# PA_Combined_RX_TX.net
KiCad netlist of a schematic drawn in Altium Designer
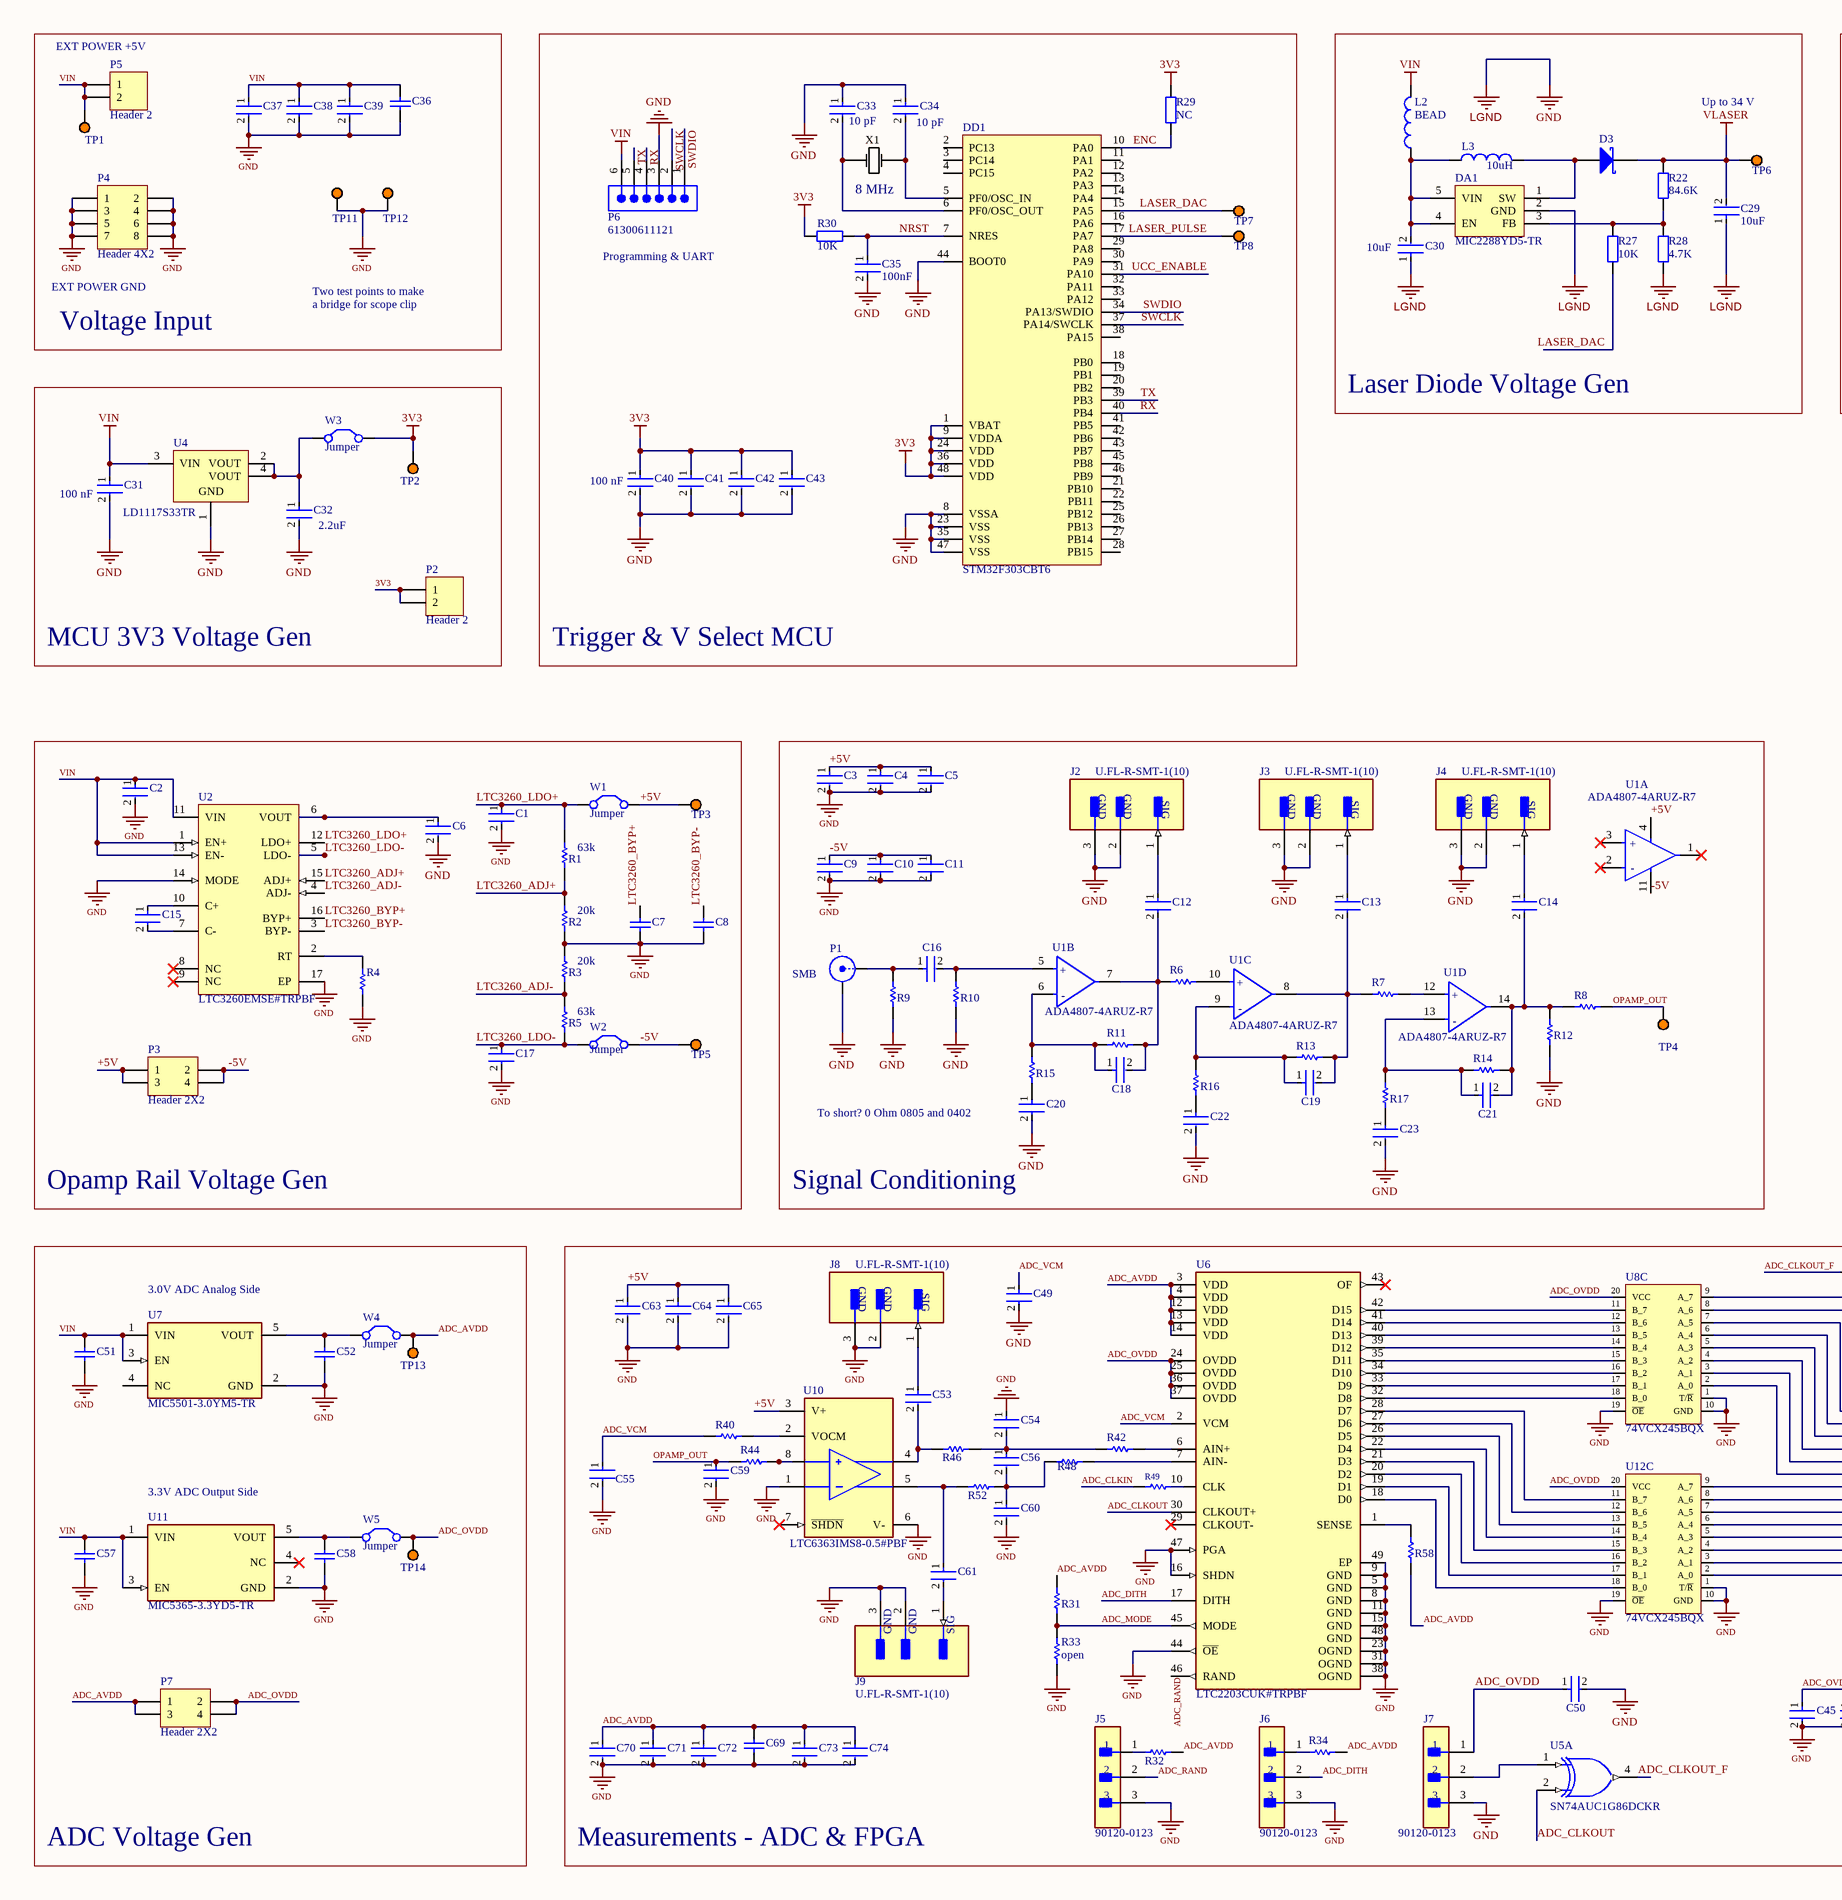
[diagram p0: PA_Combined_RX_TX.SchDoc, left]
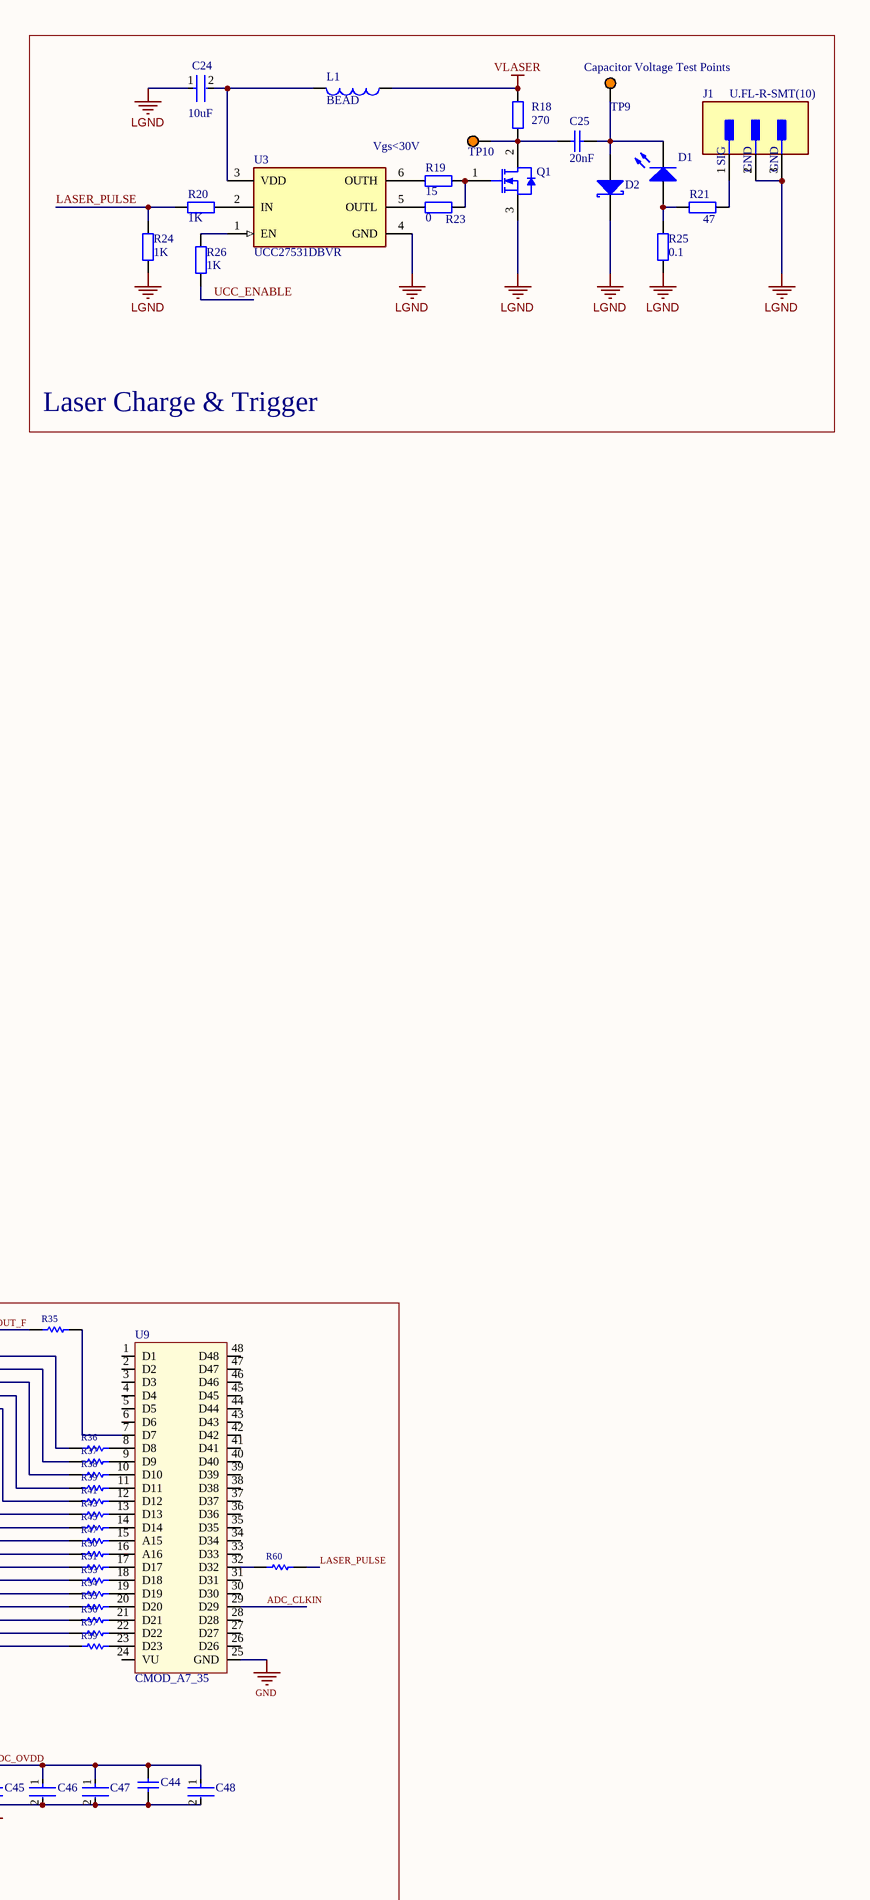
[diagram p1: PA_Combined_RX_TX.SchDoc, right]

(export (version "E")
  (design (tool "Eeschema 10.0.6"))
  (components
    (comp (ref "C1")
      (value "CL21B106KOQNNNG")
      (footprint "FP-CL21B106KOQNNNG-MFG")
      (description "CAP CER 10UF 16V X7R 0805")
      (fields
        (field (name "TOLERANCE") "10%")
        (field (name "OCTOPART") "https://octopart.com/cl21b106koqnnng-samsung-19995691")
      )
      (libsource (lib "Altium Content Vault") (part "b4654b650e69147ec39a6b967a45e02"))
    )
    (comp (ref "C2")
      (value "CL21B106KOQNNNG")
      (footprint "FP-CL21B106KOQNNNG-MFG")
      (description "CAP CER 10UF 16V X7R 0805")
      (fields
        (field (name "TOLERANCE") "10%")
        (field (name "OCTOPART") "https://octopart.com/cl21b106koqnnng-samsung-19995691")
      )
      (libsource (lib "Altium Content Vault") (part "b4654b650e69147ec39a6b967a45e02"))
    )
    (comp (ref "C3")
      (value "CL21B106KOQNNNG")
      (footprint "FP-CL21B106KOQNNNG-MFG")
      (description "CAP CER 10UF 16V X7R 0805")
      (fields
        (field (name "TOLERANCE") "10%")
        (field (name "OCTOPART") "https://octopart.com/cl21b106koqnnng-samsung-19995691")
      )
      (libsource (lib "Altium Content Vault") (part "b4654b650e69147ec39a6b967a45e02"))
    )
    (comp (ref "C4")
      (value "GRM21BR71C475KE51K")
      (footprint "FP-GRM21B-0_15-MFG")
      (description "Chip Multilayer Ceramic Capacitors for General Purpose, 0805, 4.7uF, X7R, 15%, 10%, 16V")
      (fields (field (name "TOLERANCE") "10%"))
      (libsource (lib "Altium Content Vault") (part "b4654b650e69147ec39a6b967a45e02"))
    )
    (comp (ref "C5")
      (value "C0805C104K5RACTU")
      (footprint "FP-C0805C-DN-MFG")
      (description "CAP CER 0.1UF 50V X7R 0805")
      (fields
        (field (name "MANUFACTURER") "KEMET")
        (field (name "OCTOPART") "https://octopart.com/c0805c104k5ractu-kemet-143926")
      )
      (libsource (lib "Altium Content Vault") (part "b4654b650e69147ec39a6b967a45e02"))
    )
    (comp (ref "C6")
      (value "CL21B106KOQNNNG")
      (footprint "FP-CL21B106KOQNNNG-MFG")
      (description "CAP CER 10UF 16V X7R 0805")
      (fields
        (field (name "TOLERANCE") "10%")
        (field (name "OCTOPART") "https://octopart.com/cl21b106koqnnng-samsung-19995691")
      )
      (libsource (lib "Altium Content Vault") (part "b4654b650e69147ec39a6b967a45e02"))
    )
    (comp (ref "C7")
      (value "C0805F103K5RACTU")
      (footprint "CAPC2013X100X50NL20T25")
      (fields (field (name "MANUFACTURER") "Kemet"))
      (libsource (lib "Altium Content Vault") (part "CAP"))
    )
    (comp (ref "C8")
      (value "C0805F103K5RACTU")
      (footprint "CAPC2013X100X50NL20T25")
      (fields (field (name "MANUFACTURER") "Kemet"))
      (libsource (lib "Altium Content Vault") (part "CAP"))
    )
    (comp (ref "C9")
      (value "CL21B106KOQNNNG")
      (footprint "FP-CL21B106KOQNNNG-MFG")
      (description "CAP CER 10UF 16V X7R 0805")
      (fields
        (field (name "TOLERANCE") "10%")
        (field (name "OCTOPART") "https://octopart.com/cl21b106koqnnng-samsung-19995691")
      )
      (libsource (lib "Altium Content Vault") (part "b4654b650e69147ec39a6b967a45e02"))
    )
    (comp (ref "C10")
      (value "GRM21BR71C475KE51K")
      (footprint "FP-GRM21B-0_15-MFG")
      (description "Chip Multilayer Ceramic Capacitors for General Purpose, 0805, 4.7uF, X7R, 15%, 10%, 16V")
      (fields (field (name "TOLERANCE") "10%"))
      (libsource (lib "Altium Content Vault") (part "b4654b650e69147ec39a6b967a45e02"))
    )
    (comp (ref "C11")
      (value "C0805C104K5RACTU")
      (footprint "FP-C0805C-DN-MFG")
      (description "CAP CER 0.1UF 50V X7R 0805")
      (fields
        (field (name "MANUFACTURER") "KEMET")
        (field (name "OCTOPART") "https://octopart.com/c0805c104k5ractu-kemet-143926")
      )
      (libsource (lib "Altium Content Vault") (part "b4654b650e69147ec39a6b967a45e02"))
    )
    (comp (ref "C12")
      (value "C0805C102K5RACTU")
      (footprint "FP-C0805C-DN-MFG")
      (description "CAP CER 1000PF 50V X7R 0805")
      (fields
        (field (name "OCTOPART") "https://octopart.com/c0805c102k5ractu-kemet-93010")
        (field (name "TOLERANCE") "0.1")
      )
      (libsource (lib "Altium Content Vault") (part "b4654b650e69147ec39a6b967a45e02"))
    )
    (comp (ref "C13")
      (value "C0805C102K5RACTU")
      (footprint "FP-C0805C-DN-MFG")
      (description "CAP CER 1000PF 50V X7R 0805")
      (fields
        (field (name "OCTOPART") "https://octopart.com/c0805c102k5ractu-kemet-93010")
        (field (name "TOLERANCE") "0.1")
      )
      (libsource (lib "Altium Content Vault") (part "b4654b650e69147ec39a6b967a45e02"))
    )
    (comp (ref "C14")
      (value "C0805C102K5RACTU")
      (footprint "FP-C0805C-DN-MFG")
      (description "CAP CER 1000PF 50V X7R 0805")
      (fields
        (field (name "OCTOPART") "https://octopart.com/c0805c102k5ractu-kemet-93010")
        (field (name "TOLERANCE") "0.1")
      )
      (libsource (lib "Altium Content Vault") (part "b4654b650e69147ec39a6b967a45e02"))
    )
    (comp (ref "C15")
      (value "CL21B105KAFNNNG")
      (footprint "FP-CL21-IPC_C")
      (description "CL21 Series 0805 1uF 25V ±10% Tolerance X7R Multilayer Ceramic Chip Capacitor")
      (fields (field (name "TOLERANCE") "10%") (field (name "VOLTAGE") "25V"))
      (libsource (lib "Altium Content Vault") (part "b4654b650e69147ec39a6b967a45e02"))
    )
    (comp (ref "C16")
      (value "CL21B222JBANNNC")
      (footprint "FP-CL21-IPC_B")
      (description "CL21 Series 0805 2.2nF 50V ±5% Tolerance X7R Multilayer Ceramic Chip Capacitor")
      (fields (field (name "TOLERANCE") "5%") (field (name "VOLTAGE") "50V"))
      (libsource (lib "Altium Content Vault") (part "b4654b650e69147ec39a6b967a45e02"))
    )
    (comp (ref "C17")
      (value "CL21B106KOQNNNG")
      (footprint "FP-CL21B106KOQNNNG-MFG")
      (description "CAP CER 10UF 16V X7R 0805")
      (fields
        (field (name "TOLERANCE") "10%")
        (field (name "OCTOPART") "https://octopart.com/cl21b106koqnnng-samsung-19995691")
      )
      (libsource (lib "Altium Content Vault") (part "b4654b650e69147ec39a6b967a45e02"))
    )
    (comp (ref "C18")
      (value "C0805C150K5RACTU")
      (footprint "FP-C0805C-DN-MFG")
      (description "CAP CER SMD 0805 15PF 50V 10% X7")
      (fields
        (field (name "OCTOPART") "https://octopart.com/c0805c150k5ractu-kemet-88373275")
        (field (name "MANUFACTURER") "KEMET")
      )
      (libsource (lib "Altium Content Vault") (part "b4654b650e69147ec39a6b967a45e02"))
    )
    (comp (ref "C19")
      (value "C0805C150K5RACTU")
      (footprint "FP-C0805C-DN-MFG")
      (description "CAP CER SMD 0805 15PF 50V 10% X7")
      (fields
        (field (name "OCTOPART") "https://octopart.com/c0805c150k5ractu-kemet-88373275")
        (field (name "MANUFACTURER") "KEMET")
      )
      (libsource (lib "Altium Content Vault") (part "b4654b650e69147ec39a6b967a45e02"))
    )
    (comp (ref "C20")
      (value "CL21B106KOQNNNG")
      (footprint "FP-CL21B106KOQNNNG-MFG")
      (description "CAP CER 10UF 16V X7R 0805")
      (fields
        (field (name "TOLERANCE") "10%")
        (field (name "OCTOPART") "https://octopart.com/cl21b106koqnnng-samsung-19995691")
      )
      (libsource (lib "Altium Content Vault") (part "b4654b650e69147ec39a6b967a45e02"))
    )
    (comp (ref "C21")
      (value "C0805C150K5RACTU")
      (footprint "FP-C0805C-DN-MFG")
      (description "CAP CER SMD 0805 15PF 50V 10% X7")
      (fields
        (field (name "OCTOPART") "https://octopart.com/c0805c150k5ractu-kemet-88373275")
        (field (name "MANUFACTURER") "KEMET")
      )
      (libsource (lib "Altium Content Vault") (part "b4654b650e69147ec39a6b967a45e02"))
    )
    (comp (ref "C22")
      (value "CL21B106KOQNNNG")
      (footprint "FP-CL21B106KOQNNNG-MFG")
      (description "CAP CER 10UF 16V X7R 0805")
      (fields
        (field (name "TOLERANCE") "10%")
        (field (name "OCTOPART") "https://octopart.com/cl21b106koqnnng-samsung-19995691")
      )
      (libsource (lib "Altium Content Vault") (part "b4654b650e69147ec39a6b967a45e02"))
    )
    (comp (ref "C23")
      (value "CL21B106KOQNNNG")
      (footprint "FP-CL21B106KOQNNNG-MFG")
      (description "CAP CER 10UF 16V X7R 0805")
      (fields
        (field (name "TOLERANCE") "10%")
        (field (name "OCTOPART") "https://octopart.com/cl21b106koqnnng-samsung-19995691")
      )
      (libsource (lib "Altium Content Vault") (part "b4654b650e69147ec39a6b967a45e02"))
    )
    (comp (ref "C24")
      (value "10uF")
      (footprint "FP-CL31B106KBHNNNE-MFG")
      (description "CAP CER 10UF 50V X7R 1206")
      (fields (field (name "MANUFACTURER") "Samsung") (field (name "TOLERANCE") "10%"))
      (libsource (lib "Altium Content Vault") (part "b4654b650e69147ec39a6b967a45e02"))
    )
    (comp (ref "C25")
      (value "20nF")
      (footprint "RESC2013X60X35ML10T20")
      (description "Chip capacitor")
      (fields (field (name "VOLTAGE") "50V"))
      (libsource (lib "MyLibSch") (part "CC0805"))
    )
    (comp (ref "C29")
      (value "10uF")
      (footprint "FP-CL31B106KBHNNNE-MFG")
      (description "CAP CER 10UF 50V X7R 1206")
      (fields (field (name "MANUFACTURER") "Samsung") (field (name "TOLERANCE") "10%"))
      (libsource (lib "Altium Content Vault") (part "b4654b650e69147ec39a6b967a45e02"))
    )
    (comp (ref "C30")
      (value "10uF")
      (footprint "FP-CL31B106KBHNNNE-MFG")
      (description "CAP CER 10UF 50V X7R 1206")
      (fields (field (name "MANUFACTURER") "Samsung") (field (name "TOLERANCE") "10%"))
      (libsource (lib "Altium Content Vault") (part "b4654b650e69147ec39a6b967a45e02"))
    )
    (comp (ref "C31")
      (value "100 nF")
      (footprint "FP-CC0603-DA-MFG")
      (description "CAP CER 0.1UF 16V X7R 0603")
      (fields
        (field (name "OCTOPART") "https://octopart.com/cc0603krx7r7bb104-yageo-192941")
        (field (name "TOLERANCE") "0.1")
      )
      (libsource (lib "Altium Content Vault") (part "11868f565c42a9108669ba33697ecf6"))
    )
    (comp (ref "C32")
      (value "~")
      (footprint "FP-CL10-IPC_A")
      (description "Cap Ceramic 2.2uF 10V X7R ±10% Pad SMD 0603 +125°C T/R")
      (fields (field (name "CAPACITANCE") "2.2uF") (field (name "TOLERANCE") "10%"))
      (libsource (lib "Altium Content Vault") (part "b4654b650e69147ec39a6b967a45e02"))
    )
    (comp (ref "C33")
      (value "10 pF")
      (footprint "FP-C0805C-DN-MFG")
      (description "C0805 10 pF X7R 30ppm/°C 5.00% 50 V")
      (fields
        (field (name "OCTOPART") "https://octopart.com/c0805c100j5ractu-kemet-81794931")
        (field (name "MANUFACTURER PART NUMBER") "C0805C100J5RACTU")
      )
      (libsource (lib "Altium Content Vault") (part "b4654b650e69147ec39a6b967a45e02"))
    )
    (comp (ref "C34")
      (value "10 pF")
      (footprint "FP-C0805C-DN-MFG")
      (description "C0805 10 pF X7R 30ppm/°C 5.00% 50 V")
      (fields
        (field (name "OCTOPART") "https://octopart.com/c0805c100j5ractu-kemet-81794931")
        (field (name "MANUFACTURER PART NUMBER") "C0805C100J5RACTU")
      )
      (libsource (lib "Altium Content Vault") (part "b4654b650e69147ec39a6b967a45e02"))
    )
    (comp (ref "C35")
      (value "100nF")
      (footprint "FP-CC0805-0_85-MFG")
      (description "CAP CER 0.1UF 50V X7R 0805")
      (fields (field (name "TOLERANCE") "0.1") (field (name "MANUFACTURER PART NUMBER") "CC0805KRX7R9BB104"))
      (libsource (lib "Altium Content Vault") (part "11868f565c42a9108669ba33697ecf6"))
    )
    (comp (ref "C36")
      (value "C0805C105K3RACTU")
      (footprint "CAPC2013X140X50LL20T25")
      (fields (field (name "MANUFACTURER") "Kemet"))
      (libsource (lib "Altium Content Vault") (part "CAP"))
    )
    (comp (ref "C37")
      (value "CL21B106KOQNNNG")
      (footprint "FP-CL21B106KOQNNNG-MFG")
      (description "CAP CER 10UF 16V X7R 0805")
      (fields
        (field (name "TOLERANCE") "10%")
        (field (name "OCTOPART") "https://octopart.com/cl21b106koqnnng-samsung-19995691")
      )
      (libsource (lib "Altium Content Vault") (part "b4654b650e69147ec39a6b967a45e02"))
    )
    (comp (ref "C38")
      (value "GRM21BR71C475KE51K")
      (footprint "FP-GRM21B-0_15-MFG")
      (description "Chip Multilayer Ceramic Capacitors for General Purpose, 0805, 4.7uF, X7R, 15%, 10%, 16V")
      (fields (field (name "TOLERANCE") "10%"))
      (libsource (lib "Altium Content Vault") (part "b4654b650e69147ec39a6b967a45e02"))
    )
    (comp (ref "C39")
      (value "C0805C104K5RACTU")
      (footprint "FP-C0805C-DN-MFG")
      (description "CAP CER 0.1UF 50V X7R 0805")
      (fields
        (field (name "MANUFACTURER") "KEMET")
        (field (name "OCTOPART") "https://octopart.com/c0805c104k5ractu-kemet-143926")
      )
      (libsource (lib "Altium Content Vault") (part "b4654b650e69147ec39a6b967a45e02"))
    )
    (comp (ref "C40")
      (value "CC0805KRX7R9BB104")
      (footprint "FP-CC0805-0_85-MFG")
      (description "CAP CER 0.1UF 50V X7R 0805")
      (fields
        (field (name "TOLERANCE") "0.1")
        (field (name "CAPACITANCE") "100 nF")
        (field (name "MANUFACTURER") "Yageo")
      )
      (libsource (lib "Altium Content Vault") (part "11868f565c42a9108669ba33697ecf6"))
    )
    (comp (ref "C41")
      (value "CC0805KRX7R9BB104")
      (footprint "FP-CC0805-0_85-MFG")
      (description "CAP CER 0.1UF 50V X7R 0805")
      (fields (field (name "TOLERANCE") "0.1") (field (name "MANUFACTURER") "Yageo"))
      (libsource (lib "Altium Content Vault") (part "11868f565c42a9108669ba33697ecf6"))
    )
    (comp (ref "C42")
      (value "CC0805KRX7R9BB104")
      (footprint "FP-CC0805-0_85-MFG")
      (description "CAP CER 0.1UF 50V X7R 0805")
      (fields (field (name "TOLERANCE") "0.1") (field (name "MANUFACTURER") "Yageo"))
      (libsource (lib "Altium Content Vault") (part "11868f565c42a9108669ba33697ecf6"))
    )
    (comp (ref "C43")
      (value "CC0805KRX7R9BB104")
      (footprint "FP-CC0805-0_85-MFG")
      (description "CAP CER 0.1UF 50V X7R 0805")
      (fields (field (name "TOLERANCE") "0.1") (field (name "MANUFACTURER") "Yageo"))
      (libsource (lib "Altium Content Vault") (part "11868f565c42a9108669ba33697ecf6"))
    )
    (comp (ref "C44")
      (value "C0805C105K3RACTU")
      (footprint "CAPC2013X140X50LL20T25")
      (fields (field (name "MANUFACTURER") "Kemet"))
      (libsource (lib "Altium Content Vault") (part "CAP"))
    )
    (comp (ref "C45")
      (value "CL21B106KOQNNNG")
      (footprint "FP-CL21B106KOQNNNG-MFG")
      (description "CAP CER 10UF 16V X7R 0805")
      (fields
        (field (name "TOLERANCE") "10%")
        (field (name "OCTOPART") "https://octopart.com/cl21b106koqnnng-samsung-19995691")
      )
      (libsource (lib "Altium Content Vault") (part "b4654b650e69147ec39a6b967a45e02"))
    )
    (comp (ref "C46")
      (value "GRM21BR71C475KE51K")
      (footprint "FP-GRM21B-0_15-MFG")
      (description "Chip Multilayer Ceramic Capacitors for General Purpose, 0805, 4.7uF, X7R, 15%, 10%, 16V")
      (fields (field (name "TOLERANCE") "10%"))
      (libsource (lib "Altium Content Vault") (part "b4654b650e69147ec39a6b967a45e02"))
    )
    (comp (ref "C47")
      (value "C0805C104K5RACTU")
      (footprint "FP-C0805C-DN-MFG")
      (description "CAP CER 0.1UF 50V X7R 0805")
      (fields
        (field (name "MANUFACTURER") "KEMET")
        (field (name "OCTOPART") "https://octopart.com/c0805c104k5ractu-kemet-143926")
      )
      (libsource (lib "Altium Content Vault") (part "b4654b650e69147ec39a6b967a45e02"))
    )
    (comp (ref "C48")
      (value "C0805C104K5RACTU")
      (footprint "FP-C0805C-DN-MFG")
      (description "CAP CER 0.1UF 50V X7R 0805")
      (fields
        (field (name "MANUFACTURER") "KEMET")
        (field (name "OCTOPART") "https://octopart.com/c0805c104k5ractu-kemet-143926")
      )
      (libsource (lib "Altium Content Vault") (part "b4654b650e69147ec39a6b967a45e02"))
    )
    (comp (ref "C49")
      (value "C2012X7R1C225K125AB")
      (footprint "FP-C2012-125-0_2-MFG")
      (description "Multilayer Ceramic Capacitors 2.2μF ±10% 16V X7R SMD 0805")
      (fields (field (name "TOLERANCE") "10%") (field (name "VOLTAGE") "16V"))
      (libsource (lib "Altium Content Vault") (part "b4654b650e69147ec39a6b967a45e02"))
    )
    (comp (ref "C50")
      (value "C0805C104K5RACTU")
      (footprint "FP-C0805C-DN-MFG")
      (description "CAP CER 0.1UF 50V X7R 0805")
      (fields
        (field (name "MANUFACTURER") "KEMET")
        (field (name "OCTOPART") "https://octopart.com/c0805c104k5ractu-kemet-143926")
      )
      (libsource (lib "Altium Content Vault") (part "b4654b650e69147ec39a6b967a45e02"))
    )
    (comp (ref "C51")
      (value "C0805C105K3RACTU")
      (footprint "CAPC2013X140X50LL20T25")
      (fields (field (name "MANUFACTURER") "Kemet"))
      (libsource (lib "Altium Content Vault") (part "CAP"))
    )
    (comp (ref "C52")
      (value "C0805C105K3RACTU")
      (footprint "CAPC2013X140X50LL20T25")
      (fields (field (name "MANUFACTURER") "Kemet"))
      (libsource (lib "Altium Content Vault") (part "CAP"))
    )
    (comp (ref "C53")
      (value "C0805C102K5RACTU")
      (footprint "FP-C0805C-DN-MFG")
      (description "CAP CER 1000PF 50V X7R 0805")
      (fields
        (field (name "OCTOPART") "https://octopart.com/c0805c102k5ractu-kemet-93010")
        (field (name "TOLERANCE") "0.1")
      )
      (libsource (lib "Altium Content Vault") (part "b4654b650e69147ec39a6b967a45e02"))
    )
    (comp (ref "C54")
      (value "C0805C100J5RACTU")
      (footprint "FP-C0805C-DN-MFG")
      (description "C0805 10 pF X7R 30ppm/°C 5.00% 50 V")
      (fields
        (field (name "OCTOPART") "https://octopart.com/c0805c100j5ractu-kemet-81794931")
        (field (name "MANUFACTURER") "KEMET")
      )
      (libsource (lib "Altium Content Vault") (part "b4654b650e69147ec39a6b967a45e02"))
    )
    (comp (ref "C55")
      (value "C0805C104K5RACTU")
      (footprint "FP-C0805C-DN-MFG")
      (description "CAP CER 0.1UF 50V X7R 0805")
      (fields
        (field (name "MANUFACTURER") "KEMET")
        (field (name "OCTOPART") "https://octopart.com/c0805c104k5ractu-kemet-143926")
      )
      (libsource (lib "Altium Content Vault") (part "b4654b650e69147ec39a6b967a45e02"))
    )
    (comp (ref "C56")
      (value "C0805C100J5RACTU")
      (footprint "FP-C0805C-DN-MFG")
      (description "C0805 10 pF X7R 30ppm/°C 5.00% 50 V")
      (fields
        (field (name "OCTOPART") "https://octopart.com/c0805c100j5ractu-kemet-81794931")
        (field (name "MANUFACTURER") "KEMET")
      )
      (libsource (lib "Altium Content Vault") (part "b4654b650e69147ec39a6b967a45e02"))
    )
    (comp (ref "C57")
      (value "C0805C105K3RACTU")
      (footprint "CAPC2013X140X50LL20T25")
      (fields (field (name "MANUFACTURER") "Kemet"))
      (libsource (lib "Altium Content Vault") (part "CAP"))
    )
    (comp (ref "C58")
      (value "C0805C105K3RACTU")
      (footprint "CAPC2013X140X50LL20T25")
      (fields (field (name "MANUFACTURER") "Kemet"))
      (libsource (lib "Altium Content Vault") (part "CAP"))
    )
    (comp (ref "C59")
      (value "C0805C100J5RACTU")
      (footprint "FP-C0805C-DN-MFG")
      (description "C0805 10 pF X7R 30ppm/°C 5.00% 50 V")
      (fields
        (field (name "OCTOPART") "https://octopart.com/c0805c100j5ractu-kemet-81794931")
        (field (name "MANUFACTURER") "KEMET")
      )
      (libsource (lib "Altium Content Vault") (part "b4654b650e69147ec39a6b967a45e02"))
    )
    (comp (ref "C60")
      (value "C0805C100J5RACTU")
      (footprint "FP-C0805C-DN-MFG")
      (description "C0805 10 pF X7R 30ppm/°C 5.00% 50 V")
      (fields
        (field (name "OCTOPART") "https://octopart.com/c0805c100j5ractu-kemet-81794931")
        (field (name "MANUFACTURER") "KEMET")
      )
      (libsource (lib "Altium Content Vault") (part "b4654b650e69147ec39a6b967a45e02"))
    )
    (comp (ref "C61")
      (value "C0805C102K5RACTU")
      (footprint "FP-C0805C-DN-MFG")
      (description "CAP CER 1000PF 50V X7R 0805")
      (fields
        (field (name "OCTOPART") "https://octopart.com/c0805c102k5ractu-kemet-93010")
        (field (name "TOLERANCE") "0.1")
      )
      (libsource (lib "Altium Content Vault") (part "b4654b650e69147ec39a6b967a45e02"))
    )
    (comp (ref "C63")
      (value "CL21B106KOQNNNG")
      (footprint "FP-CL21B106KOQNNNG-MFG")
      (description "CAP CER 10UF 16V X7R 0805")
      (fields
        (field (name "TOLERANCE") "10%")
        (field (name "OCTOPART") "https://octopart.com/cl21b106koqnnng-samsung-19995691")
      )
      (libsource (lib "Altium Content Vault") (part "b4654b650e69147ec39a6b967a45e02"))
    )
    (comp (ref "C64")
      (value "GRM21BR71C475KE51K")
      (footprint "FP-GRM21B-0_15-MFG")
      (description "Chip Multilayer Ceramic Capacitors for General Purpose, 0805, 4.7uF, X7R, 15%, 10%, 16V")
      (fields (field (name "TOLERANCE") "10%"))
      (libsource (lib "Altium Content Vault") (part "b4654b650e69147ec39a6b967a45e02"))
    )
    (comp (ref "C65")
      (value "C0805C104K5RACTU")
      (footprint "FP-C0805C-DN-MFG")
      (description "CAP CER 0.1UF 50V X7R 0805")
      (fields
        (field (name "MANUFACTURER") "KEMET")
        (field (name "OCTOPART") "https://octopart.com/c0805c104k5ractu-kemet-143926")
      )
      (libsource (lib "Altium Content Vault") (part "b4654b650e69147ec39a6b967a45e02"))
    )
    (comp (ref "C69")
      (value "C0805C105K3RACTU")
      (footprint "CAPC2013X140X50LL20T25")
      (fields (field (name "MANUFACTURER") "Kemet"))
      (libsource (lib "Altium Content Vault") (part "CAP"))
    )
    (comp (ref "C70")
      (value "CL21B106KOQNNNG")
      (footprint "FP-CL21B106KOQNNNG-MFG")
      (description "CAP CER 10UF 16V X7R 0805")
      (fields
        (field (name "TOLERANCE") "10%")
        (field (name "OCTOPART") "https://octopart.com/cl21b106koqnnng-samsung-19995691")
      )
      (libsource (lib "Altium Content Vault") (part "b4654b650e69147ec39a6b967a45e02"))
    )
    (comp (ref "C71")
      (value "GRM21BR71C475KE51K")
      (footprint "FP-GRM21B-0_15-MFG")
      (description "Chip Multilayer Ceramic Capacitors for General Purpose, 0805, 4.7uF, X7R, 15%, 10%, 16V")
      (fields (field (name "TOLERANCE") "10%"))
      (libsource (lib "Altium Content Vault") (part "b4654b650e69147ec39a6b967a45e02"))
    )
    (comp (ref "C72")
      (value "C0805C104K5RACTU")
      (footprint "FP-C0805C-DN-MFG")
      (description "CAP CER 0.1UF 50V X7R 0805")
      (fields
        (field (name "MANUFACTURER") "KEMET")
        (field (name "OCTOPART") "https://octopart.com/c0805c104k5ractu-kemet-143926")
      )
      (libsource (lib "Altium Content Vault") (part "b4654b650e69147ec39a6b967a45e02"))
    )
    (comp (ref "C73")
      (value "C0805C104K5RACTU")
      (footprint "FP-C0805C-DN-MFG")
      (description "CAP CER 0.1UF 50V X7R 0805")
      (fields
        (field (name "MANUFACTURER") "KEMET")
        (field (name "OCTOPART") "https://octopart.com/c0805c104k5ractu-kemet-143926")
      )
      (libsource (lib "Altium Content Vault") (part "b4654b650e69147ec39a6b967a45e02"))
    )
    (comp (ref "C74")
      (value "C0805C104K5RACTU")
      (footprint "FP-C0805C-DN-MFG")
      (description "CAP CER 0.1UF 50V X7R 0805")
      (fields
        (field (name "MANUFACTURER") "KEMET")
        (field (name "OCTOPART") "https://octopart.com/c0805c104k5ractu-kemet-143926")
      )
      (libsource (lib "Altium Content Vault") (part "b4654b650e69147ec39a6b967a45e02"))
    )
    (comp (ref "D1")
      (value "Light-Emitting Diode")
      (footprint "FP-DPGEW1S09H-MFG")
      (libsource (lib "Simulation Generic Components") (part "LED"))
    )
    (comp (ref "D2")
      (value "Schottky Diode")
      (footprint "FP-PG-SC79-2-MFG")
      (libsource (lib "Simulation Generic Components") (part "Schottky Diode"))
    )
    (comp (ref "D3")
      (value "Schottky Diode")
      (footprint "FP-PG-SC79-2-MFG")
      (libsource (lib "Simulation Generic Components") (part "Schottky Diode"))
    )
    (comp (ref "DA1")
      (value "MIC2288YD5-TR")
      (footprint "TSOT-23-5:FP-TSOT-5LD-PL-1-IPC_A")
      (description "Step Up")
      (libsource (lib "lcd_lib") (part "MIC2288"))
    )
    (comp (ref "DD1")
      (value "STM32F303CBT6")
      (footprint "STM-LQFP48_L")
      (description "Microcontroller")
      (libsource (lib "lcd_lib") (part "STM32F3_LQFP48"))
    )
    (comp (ref "J1")
      (value "U.FL-R-SMT(10)")
      (footprint "FP-U_FL-R-SMT_10-MFG")
      (description "CONN U.FL RCPT STR 50 OHM SMD")
      (libsource (lib "Altium Content Vault") (part "eef6fde44c591823e8076210edfe12f"))
    )
    (comp (ref "J2")
      (value "U.FL-R-SMT-1(10)")
      (footprint "FP-U_FL-R-SMT-1_10-MFG")
      (description "CONN U.FL RCPT STR 50 OHM SMD")
      (libsource (lib "Altium Content Vault") (part "7158abf7d987fa84906f6fb0d115710"))
    )
    (comp (ref "J3")
      (value "U.FL-R-SMT-1(10)")
      (footprint "FP-U_FL-R-SMT-1_10-MFG")
      (description "CONN U.FL RCPT STR 50 OHM SMD")
      (libsource (lib "Altium Content Vault") (part "7158abf7d987fa84906f6fb0d115710"))
    )
    (comp (ref "J4")
      (value "U.FL-R-SMT-1(10)")
      (footprint "FP-U_FL-R-SMT-1_10-MFG")
      (description "CONN U.FL RCPT STR 50 OHM SMD")
      (libsource (lib "Altium Content Vault") (part "7158abf7d987fa84906f6fb0d115710"))
    )
    (comp (ref "J5")
      (value "90120-0123")
      (footprint "FP-90120-0123-MFG")
      (description "CONN HEADER VERT 3POS 2.54MM")
      (libsource (lib "Altium Content Vault") (part "0d3f023dd272f625e17a2be33dea85f"))
    )
    (comp (ref "J6")
      (value "90120-0123")
      (footprint "FP-90120-0123-MFG")
      (description "CONN HEADER VERT 3POS 2.54MM")
      (libsource (lib "Altium Content Vault") (part "0d3f023dd272f625e17a2be33dea85f"))
    )
    (comp (ref "J7")
      (value "90120-0123")
      (footprint "FP-90120-0123-MFG")
      (description "CONN HEADER VERT 3POS 2.54MM")
      (libsource (lib "Altium Content Vault") (part "0d3f023dd272f625e17a2be33dea85f"))
    )
    (comp (ref "J8")
      (value "U.FL-R-SMT-1(10)")
      (footprint "FP-U_FL-R-SMT-1_10-MFG")
      (description "CONN U.FL RCPT STR 50 OHM SMD")
      (libsource (lib "Altium Content Vault") (part "7158abf7d987fa84906f6fb0d115710"))
    )
    (comp (ref "J9")
      (value "U.FL-R-SMT-1(10)")
      (footprint "FP-U_FL-R-SMT-1_10-MFG")
      (description "CONN U.FL RCPT STR 50 OHM SMD")
      (libsource (lib "") (part "7158abf7d987fa84906f6fb0d115710_1"))
    )
    (comp (ref "L1")
      (value "BEAD")
      (footprint "FP-BLM18-0_15-t0_8-IPC_A")
      (description "Ferrit Bead")
      (libsource (lib "MyLibSch") (part "BEAD"))
    )
    (comp (ref "L2")
      (value "BEAD")
      (footprint "FP-BLM18-0_15-t0_8-IPC_A")
      (description "Ferrit Bead")
      (libsource (lib "MyLibSch") (part "BEAD"))
    )
    (comp (ref "L3")
      (value "10uH")
      (footprint "RESC2013X60X35LL10T20")
      (description "Inductor")
      (libsource (lib "Simulation Generic Components") (part "Inductor"))
    )
    (comp (ref "P1")
      (value "SMB")
      (footprint "SMB_V-RJ45")
      (description "SMB Straight Connector")
      (fields (field (name "PUBLISHER") "Altium Limited"))
      (libsource (lib "Miscellaneous Connectors") (part "SMB"))
    )
    (comp (ref "P2")
      (value "Header 2")
      (footprint "HDR1X2")
      (description "Header, 2-Pin")
      (fields (field (name "PUBLISHER") "Altium Limited"))
      (libsource (lib "Miscellaneous Connectors") (part "Header 2"))
    )
    (comp (ref "P3")
      (value "Header 2X2")
      (footprint "HDR2X2")
      (description "Header, 2-Pin, Dual row")
      (fields (field (name "PUBLISHER") "Altium Limited"))
      (libsource (lib "Miscellaneous Connectors") (part "Header 2X2"))
    )
    (comp (ref "P4")
      (value "Header 4X2")
      (footprint "HDR2X4")
      (description "Header, 4-Pin, Dual row")
      (fields (field (name "PUBLISHER") "Altium Limited"))
      (libsource (lib "Miscellaneous Connectors") (part "Header 4X2"))
    )
    (comp (ref "P5")
      (value "Header 2")
      (footprint "HDR1X2")
      (description "Header, 2-Pin")
      (fields (field (name "PUBLISHER") "Altium Limited"))
      (libsource (lib "Miscellaneous Connectors") (part "Header 2"))
    )
    (comp (ref "P6")
      (value "61300611121")
      (footprint "61300611121")
      (libsource (lib "Altium Content Vault") (part "Header_Male_1R_06P"))
    )
    (comp (ref "P7")
      (value "Header 2X2")
      (footprint "HDR2X2")
      (description "Header, 2-Pin, Dual row")
      (fields (field (name "PUBLISHER") "Altium Limited"))
      (libsource (lib "Miscellaneous Connectors") (part "Header 2X2"))
    )
    (comp (ref "Q1")
      (value "~")
      (footprint "INF-PG-TO252-3-313_N")
      (fields (field (name "MANUFACTURER") "Infineon") (field (name "PARTNUMBER") "IPD60R520C6"))
      (libsource (lib "Components - 15.04.25 - 21.51") (part "CMP-1164-00353-1"))
    )
    (comp (ref "R1")
      (value "63k")
      (footprint "RESC2013X60X30ML20T20")
      (fields (field (name "PART NUMBER") "RK73B2ATTD510J") (field (name "MANUFACTURER") "KOA Speer"))
      (libsource (lib "Altium Content Vault") (part "RES"))
    )
    (comp (ref "R2")
      (value "20k")
      (footprint "RESC2013X60X30ML20T20")
      (fields (field (name "PART NUMBER") "RK73B2ATTD510J") (field (name "MANUFACTURER") "KOA Speer"))
      (libsource (lib "Altium Content Vault") (part "RES"))
    )
    (comp (ref "R3")
      (value "20k")
      (footprint "RESC2013X60X30ML20T20")
      (fields (field (name "PART NUMBER") "RK73B2ATTD510J") (field (name "MANUFACTURER") "KOA Speer"))
      (libsource (lib "Altium Content Vault") (part "RES"))
    )
    (comp (ref "R4")
      (value "CRCW0805200KFKEA")
      (footprint "RESC2013X50X30NL20T20")
      (fields (field (name "MANUFACTURER") "Vishay Dale"))
      (libsource (lib "Altium Content Vault") (part "RES"))
    )
    (comp (ref "R5")
      (value "63k")
      (footprint "RESC2013X60X30ML20T20")
      (fields (field (name "PART NUMBER") "RK73B2ATTD510J") (field (name "MANUFACTURER") "KOA Speer"))
      (libsource (lib "Altium Content Vault") (part "RES"))
    )
    (comp (ref "R6")
      (value "RC0805FR-071KL")
      (footprint "RESC2013X60X35ML10T20")
      (description "Chip Resistor, 1 KOhm, +/- 1%, 125 mW, -55 to 155 degC, 0805 (2012 Metric), RoHS, Tape and Reel")
      (fields (field (name "TOLERANCE") "1%") (field (name "MANUFACTURER") "Yageo"))
      (libsource (lib "Altium Content Vault") (part "RES-2"))
    )
    (comp (ref "R7")
      (value "RC0805FR-071KL")
      (footprint "RESC2013X60X35ML10T20")
      (description "Chip Resistor, 1 KOhm, +/- 1%, 125 mW, -55 to 155 degC, 0805 (2012 Metric), RoHS, Tape and Reel")
      (fields (field (name "TOLERANCE") "1%") (field (name "MANUFACTURER") "Yageo"))
      (libsource (lib "Altium Content Vault") (part "RES-2"))
    )
    (comp (ref "R8")
      (value "ERJ-6GEY0R00V")
      (footprint "RESC2013X70X40NL20T20")
      (description "Chip Resistor, 0 Ohm, +/- 1%, 0.125 W, -55 to 155 degC, 0805 (2012 Metric), RoHS, Tape and Reel")
      (fields (field (name "TOLERANCE") "5%"))
      (libsource (lib "Altium Content Vault") (part "RES-2"))
    )
    (comp (ref "R9")
      (value "RK73B2ATTD510J")
      (footprint "RESC2013X60X30ML20T20")
      (fields (field (name "MANUFACTURER") "KOA Speer"))
      (libsource (lib "Altium Content Vault") (part "RES"))
    )
    (comp (ref "R10")
      (value "RK73B2ATTD510J")
      (footprint "RESC2013X60X30ML20T20")
      (fields (field (name "MANUFACTURER") "KOA Speer"))
      (libsource (lib "Altium Content Vault") (part "RES"))
    )
    (comp (ref "R11")
      (value "RC0805FR-071KL")
      (footprint "RESC2013X60X35ML10T20")
      (description "Chip Resistor, 1 KOhm, +/- 1%, 125 mW, -55 to 155 degC, 0805 (2012 Metric), RoHS, Tape and Reel")
      (fields (field (name "TOLERANCE") "1%") (field (name "MANUFACTURER") "Yageo"))
      (libsource (lib "Altium Content Vault") (part "RES-2"))
    )
    (comp (ref "R12")
      (value "RK73B2ATTD510J")
      (footprint "RESC2013X60X30ML20T20")
      (fields (field (name "MANUFACTURER") "KOA Speer"))
      (libsource (lib "Altium Content Vault") (part "RES"))
    )
    (comp (ref "R13")
      (value "RC0805FR-071KL")
      (footprint "RESC2013X60X35ML10T20")
      (description "Chip Resistor, 1 KOhm, +/- 1%, 125 mW, -55 to 155 degC, 0805 (2012 Metric), RoHS, Tape and Reel")
      (fields (field (name "TOLERANCE") "1%") (field (name "MANUFACTURER") "Yageo"))
      (libsource (lib "Altium Content Vault") (part "RES-2"))
    )
    (comp (ref "R14")
      (value "RC0805FR-071KL")
      (footprint "RESC2013X60X35ML10T20")
      (description "Chip Resistor, 1 KOhm, +/- 1%, 125 mW, -55 to 155 degC, 0805 (2012 Metric), RoHS, Tape and Reel")
      (fields (field (name "TOLERANCE") "1%") (field (name "MANUFACTURER") "Yageo"))
      (libsource (lib "Altium Content Vault") (part "RES-2"))
    )
    (comp (ref "R15")
      (value "RC0805FR-07100RL")
      (footprint "RESC2013X60X35ML10T20")
      (description "Chip Resistor, 100 Ohm, +/-1%, 0.125 W, -55 to 155 degC, 0805 (2012 Metric), RoHS, Tape and Reel")
      (fields (field (name "TOLERANCE") "1%") (field (name "MANUFACTURER") "Yageo"))
      (libsource (lib "Altium Content Vault") (part "RES-2"))
    )
    (comp (ref "R16")
      (value "RC0805FR-07100RL")
      (footprint "RESC2013X60X35ML10T20")
      (description "Chip Resistor, 100 Ohm, +/-1%, 0.125 W, -55 to 155 degC, 0805 (2012 Metric), RoHS, Tape and Reel")
      (fields (field (name "TOLERANCE") "1%") (field (name "MANUFACTURER") "Yageo"))
      (libsource (lib "Altium Content Vault") (part "RES-2"))
    )
    (comp (ref "R17")
      (value "RC0805FR-07100RL")
      (footprint "RESC2013X60X35ML10T20")
      (description "Chip Resistor, 100 Ohm, +/-1%, 0.125 W, -55 to 155 degC, 0805 (2012 Metric), RoHS, Tape and Reel")
      (fields (field (name "TOLERANCE") "1%") (field (name "MANUFACTURER") "Yageo"))
      (libsource (lib "Altium Content Vault") (part "RES-2"))
    )
    (comp (ref "R18")
      (value "270")
      (footprint "FP-CL31B106KBHNNNE-IPC_A")
      (description "Chip resistor")
      (fields (field (name "TOLERANCE") "5%"))
      (libsource (lib "MyLibSch") (part "RC0805"))
    )
    (comp (ref "R19")
      (value "15")
      (footprint "RESC2013X60X35ML10T20")
      (description "Chip resistor")
      (fields (field (name "TOLERANCE") "5%"))
      (libsource (lib "") (part "RC0805_3"))
    )
    (comp (ref "R20")
      (value "1K")
      (footprint "RESC2013X60X35ML10T20")
      (description "Chip resistor")
      (fields (field (name "TOLERANCE") "5%"))
      (libsource (lib "") (part "RC0805_3"))
    )
    (comp (ref "R21")
      (value "47")
      (footprint "RESC2013X60X35ML10T20")
      (description "Chip resistor")
      (fields (field (name "TOLERANCE") "5%"))
      (libsource (lib "") (part "RC0805_1"))
    )
    (comp (ref "R22")
      (value "84.6K")
      (footprint "RESC2013X60X35ML10T20")
      (description "Chip resistor")
      (fields (field (name "TOLERANCE") "5%"))
      (libsource (lib "MyLibSch") (part "RC0805"))
    )
    (comp (ref "R23")
      (value "0")
      (footprint "RESC2013X60X35ML10T20")
      (description "Chip resistor")
      (fields (field (name "TOLERANCE") "5%"))
      (libsource (lib "") (part "RC0805_3"))
    )
    (comp (ref "R24")
      (value "1K")
      (footprint "RESC2013X60X35ML10T20")
      (description "Chip resistor")
      (fields (field (name "TOLERANCE") "5%"))
      (libsource (lib "MyLibSch") (part "RC0805"))
    )
    (comp (ref "R25")
      (value "0.1")
      (footprint "RESC2013X60X35NL10T20")
      (description "Chip resistor")
      (fields (field (name "TOLERANCE") "5%"))
      (libsource (lib "MyLibSch") (part "RC0805"))
    )
    (comp (ref "R26")
      (value "1K")
      (footprint "RESC2013X60X35ML10T20")
      (description "Chip resistor")
      (fields (field (name "TOLERANCE") "5%"))
      (libsource (lib "MyLibSch") (part "RC0805"))
    )
    (comp (ref "R27")
      (value "10K")
      (footprint "RESC2013X60X35ML10T20")
      (description "Chip resistor")
      (fields (field (name "TOLERANCE") "5%"))
      (libsource (lib "MyLibSch") (part "RC0805"))
    )
    (comp (ref "R28")
      (value "4.7K")
      (footprint "RESC2013X60X35ML10T20")
      (description "Chip resistor")
      (fields (field (name "TOLERANCE") "5%"))
      (libsource (lib "MyLibSch") (part "RC0805"))
    )
    (comp (ref "R29")
      (value "NC")
      (footprint "RESC2013X60X35ML10T20")
      (description "Chip resistor")
      (fields (field (name "TOLERANCE") "5%"))
      (libsource (lib "") (part "RC0805_2"))
    )
    (comp (ref "R30")
      (value "10K")
      (footprint "RESC2013X60X35ML10T20")
      (description "Chip resistor")
      (fields (field (name "TOLERANCE") "5%"))
      (libsource (lib "") (part "RC0805_1"))
    )
    (comp (ref "R31")
      (value "RC0805FR-071KL")
      (footprint "RESC2013X60X35ML10T20")
      (description "Chip Resistor, 1 KOhm, +/- 1%, 125 mW, -55 to 155 degC, 0805 (2012 Metric), RoHS, Tape and Reel")
      (fields (field (name "TOLERANCE") "1%") (field (name "MANUFACTURER") "Yageo"))
      (libsource (lib "Altium Content Vault") (part "RES-2"))
    )
    (comp (ref "R32")
      (value "RK73H2ATTD1002F")
      (footprint "RESC2013X60X30LL20T20")
      (fields (field (name "MANUFACTURER") "KOA Speer"))
      (libsource (lib "Altium Content Vault") (part "RES"))
    )
    (comp (ref "R33")
      (value "open")
      (footprint "RESC2013X60X35LL10T20")
      (description "Resistor")
      (libsource (lib "Simulation Generic Components") (part "Resistor"))
    )
    (comp (ref "R34")
      (value "RK73H2ATTD1002F")
      (footprint "RESC2013X60X30LL20T20")
      (fields (field (name "MANUFACTURER") "KOA Speer"))
      (libsource (lib "Altium Content Vault") (part "RES"))
    )
    (comp (ref "R35")
      (value "RC0805FR-0733RL")
      (footprint "RESC2013X60X35LL10T20")
      (description "Chip Resistor, 33 Ohm, +/- 1%, 0.125 W, -55 to 155 degC, 0805 (2012 Metric), RoHS, Tape and Reel")
      (fields (field (name "MANUFACTURER") "Yageo"))
      (libsource (lib "Altium Content Vault") (part "RES-2"))
    )
    (comp (ref "R36")
      (value "RC0805FR-0733RL")
      (footprint "RESC2013X60X35LL10T20")
      (description "Chip Resistor, 33 Ohm, +/- 1%, 0.125 W, -55 to 155 degC, 0805 (2012 Metric), RoHS, Tape and Reel")
      (fields (field (name "MANUFACTURER") "Yageo"))
      (libsource (lib "Altium Content Vault") (part "RES-2"))
    )
    (comp (ref "R37")
      (value "RC0805FR-0733RL")
      (footprint "RESC2013X60X35LL10T20")
      (description "Chip Resistor, 33 Ohm, +/- 1%, 0.125 W, -55 to 155 degC, 0805 (2012 Metric), RoHS, Tape and Reel")
      (fields (field (name "MANUFACTURER") "Yageo"))
      (libsource (lib "Altium Content Vault") (part "RES-2"))
    )
    (comp (ref "R38")
      (value "RC0805FR-0733RL")
      (footprint "RESC2013X60X35LL10T20")
      (description "Chip Resistor, 33 Ohm, +/- 1%, 0.125 W, -55 to 155 degC, 0805 (2012 Metric), RoHS, Tape and Reel")
      (fields (field (name "MANUFACTURER") "Yageo"))
      (libsource (lib "Altium Content Vault") (part "RES-2"))
    )
    (comp (ref "R39")
      (value "RC0805FR-0733RL")
      (footprint "RESC2013X60X35LL10T20")
      (description "Chip Resistor, 33 Ohm, +/- 1%, 0.125 W, -55 to 155 degC, 0805 (2012 Metric), RoHS, Tape and Reel")
      (fields (field (name "MANUFACTURER") "Yageo"))
      (libsource (lib "Altium Content Vault") (part "RES-2"))
    )
    (comp (ref "R40")
      (value "RC0805FR-07100RL")
      (footprint "RESC2013X60X35ML10T20")
      (description "Chip Resistor, 100 Ohm, +/-1%, 0.125 W, -55 to 155 degC, 0805 (2012 Metric), RoHS, Tape and Reel")
      (fields (field (name "TOLERANCE") "1%") (field (name "MANUFACTURER") "Yageo"))
      (libsource (lib "Altium Content Vault") (part "RES-2"))
    )
    (comp (ref "R41")
      (value "RC0805FR-0733RL")
      (footprint "RESC2013X60X35LL10T20")
      (description "Chip Resistor, 33 Ohm, +/- 1%, 0.125 W, -55 to 155 degC, 0805 (2012 Metric), RoHS, Tape and Reel")
      (fields (field (name "MANUFACTURER") "Yageo"))
      (libsource (lib "Altium Content Vault") (part "RES-2"))
    )
    (comp (ref "R42")
      (value "RC0805JR-075R1L")
      (footprint "RESC2013X60X35LL10T20")
      (fields (field (name "MANUFACTURER") "Yageo"))
      (libsource (lib "Altium Content Vault") (part "RES"))
    )
    (comp (ref "R43")
      (value "RC0805FR-0733RL")
      (footprint "RESC2013X60X35LL10T20")
      (description "Chip Resistor, 33 Ohm, +/- 1%, 0.125 W, -55 to 155 degC, 0805 (2012 Metric), RoHS, Tape and Reel")
      (fields (field (name "MANUFACTURER") "Yageo"))
      (libsource (lib "Altium Content Vault") (part "RES-2"))
    )
    (comp (ref "R44")
      (value "ERJ-6GEY0R00V")
      (footprint "RESC2013X70X40NL20T20")
      (description "Chip Resistor, 0 Ohm, +/- 1%, 0.125 W, -55 to 155 degC, 0805 (2012 Metric), RoHS, Tape and Reel")
      (fields (field (name "TOLERANCE") "5%"))
      (libsource (lib "Altium Content Vault") (part "RES-2"))
    )
    (comp (ref "R45")
      (value "RC0805FR-0733RL")
      (footprint "RESC2013X60X35LL10T20")
      (description "Chip Resistor, 33 Ohm, +/- 1%, 0.125 W, -55 to 155 degC, 0805 (2012 Metric), RoHS, Tape and Reel")
      (fields (field (name "MANUFACTURER") "Yageo"))
      (libsource (lib "Altium Content Vault") (part "RES-2"))
    )
    (comp (ref "R46")
      (value "RK73B2ATTD510J")
      (footprint "RESC2013X60X30ML20T20")
      (fields (field (name "MANUFACTURER") "KOA Speer"))
      (libsource (lib "Altium Content Vault") (part "RES"))
    )
    (comp (ref "R47")
      (value "RC0805FR-0733RL")
      (footprint "RESC2013X60X35LL10T20")
      (description "Chip Resistor, 33 Ohm, +/- 1%, 0.125 W, -55 to 155 degC, 0805 (2012 Metric), RoHS, Tape and Reel")
      (fields (field (name "MANUFACTURER") "Yageo"))
      (libsource (lib "Altium Content Vault") (part "RES-2"))
    )
    (comp (ref "R48")
      (value "RC0805JR-075R1L")
      (footprint "RESC2013X60X35LL10T20")
      (fields (field (name "MANUFACTURER") "Yageo"))
      (libsource (lib "Altium Content Vault") (part "RES"))
    )
    (comp (ref "R49")
      (value "RC0805FR-0733RL")
      (footprint "RESC2013X60X35LL10T20")
      (description "Chip Resistor, 33 Ohm, +/- 1%, 0.125 W, -55 to 155 degC, 0805 (2012 Metric), RoHS, Tape and Reel")
      (fields (field (name "MANUFACTURER") "Yageo"))
      (libsource (lib "Altium Content Vault") (part "RES-2"))
    )
    (comp (ref "R50")
      (value "RC0805FR-0733RL")
      (footprint "RESC2013X60X35LL10T20")
      (description "Chip Resistor, 33 Ohm, +/- 1%, 0.125 W, -55 to 155 degC, 0805 (2012 Metric), RoHS, Tape and Reel")
      (fields (field (name "MANUFACTURER") "Yageo"))
      (libsource (lib "Altium Content Vault") (part "RES-2"))
    )
    (comp (ref "R51")
      (value "RC0805FR-0733RL")
      (footprint "RESC2013X60X35LL10T20")
      (description "Chip Resistor, 33 Ohm, +/- 1%, 0.125 W, -55 to 155 degC, 0805 (2012 Metric), RoHS, Tape and Reel")
      (fields (field (name "MANUFACTURER") "Yageo"))
      (libsource (lib "Altium Content Vault") (part "RES-2"))
    )
    (comp (ref "R52")
      (value "RK73B2ATTD510J")
      (footprint "RESC2013X60X30ML20T20")
      (fields (field (name "MANUFACTURER") "KOA Speer"))
      (libsource (lib "Altium Content Vault") (part "RES"))
    )
    (comp (ref "R53")
      (value "RC0805FR-0733RL")
      (footprint "RESC2013X60X35LL10T20")
      (description "Chip Resistor, 33 Ohm, +/- 1%, 0.125 W, -55 to 155 degC, 0805 (2012 Metric), RoHS, Tape and Reel")
      (fields (field (name "MANUFACTURER") "Yageo"))
      (libsource (lib "Altium Content Vault") (part "RES-2"))
    )
    (comp (ref "R54")
      (value "RC0805FR-0733RL")
      (footprint "RESC2013X60X35LL10T20")
      (description "Chip Resistor, 33 Ohm, +/- 1%, 0.125 W, -55 to 155 degC, 0805 (2012 Metric), RoHS, Tape and Reel")
      (fields (field (name "MANUFACTURER") "Yageo"))
      (libsource (lib "Altium Content Vault") (part "RES-2"))
    )
    (comp (ref "R55")
      (value "RC0805FR-0733RL")
      (footprint "RESC2013X60X35LL10T20")
      (description "Chip Resistor, 33 Ohm, +/- 1%, 0.125 W, -55 to 155 degC, 0805 (2012 Metric), RoHS, Tape and Reel")
      (fields (field (name "MANUFACTURER") "Yageo"))
      (libsource (lib "Altium Content Vault") (part "RES-2"))
    )
    (comp (ref "R56")
      (value "RC0805FR-0733RL")
      (footprint "RESC2013X60X35LL10T20")
      (description "Chip Resistor, 33 Ohm, +/- 1%, 0.125 W, -55 to 155 degC, 0805 (2012 Metric), RoHS, Tape and Reel")
      (fields (field (name "MANUFACTURER") "Yageo"))
      (libsource (lib "Altium Content Vault") (part "RES-2"))
    )
    (comp (ref "R57")
      (value "RC0805FR-0733RL")
      (footprint "RESC2013X60X35LL10T20")
      (description "Chip Resistor, 33 Ohm, +/- 1%, 0.125 W, -55 to 155 degC, 0805 (2012 Metric), RoHS, Tape and Reel")
      (fields (field (name "MANUFACTURER") "Yageo"))
      (libsource (lib "Altium Content Vault") (part "RES-2"))
    )
    (comp (ref "R58")
      (value "RK73H2ATTD10R0F")
      (footprint "RESC2013X60X30ML20T20")
      (fields (field (name "MANUFACTURER") "KOA Speer"))
      (libsource (lib "Altium Content Vault") (part "RES"))
    )
    (comp (ref "R59")
      (value "RC0805FR-0733RL")
      (footprint "RESC2013X60X35LL10T20")
      (description "Chip Resistor, 33 Ohm, +/- 1%, 0.125 W, -55 to 155 degC, 0805 (2012 Metric), RoHS, Tape and Reel")
      (fields (field (name "MANUFACTURER") "Yageo"))
      (libsource (lib "Altium Content Vault") (part "RES-2"))
    )
    (comp (ref "R60")
      (value "RC0805FR-0733RL")
      (footprint "RESC2013X60X35LL10T20")
      (description "Chip Resistor, 33 Ohm, +/- 1%, 0.125 W, -55 to 155 degC, 0805 (2012 Metric), RoHS, Tape and Reel")
      (fields (field (name "MANUFACTURER") "Yageo"))
      (libsource (lib "Altium Content Vault") (part "RES-2"))
    )
    (comp (ref "TP1")
      (value "5003")
      (footprint "EE209_PcbLib:TP_TH")
      (description "Test Point, Orange, 1-Pin THD, RoHS")
      (libsource (lib "EE209_SchLib") (part "TestPoint"))
    )
    (comp (ref "TP2")
      (value "5003")
      (footprint "EE209_PcbLib:TP_TH")
      (description "Test Point, Orange, 1-Pin THD, RoHS")
      (libsource (lib "EE209_SchLib") (part "TestPoint"))
    )
    (comp (ref "TP3")
      (value "5003")
      (footprint "EE209_PcbLib:TP_TH")
      (description "Test Point, Orange, 1-Pin THD, RoHS")
      (libsource (lib "EE209_SchLib") (part "TestPoint"))
    )
    (comp (ref "TP4")
      (value "5003")
      (footprint "EE209_PcbLib:TP_TH")
      (description "Test Point, Orange, 1-Pin THD, RoHS")
      (libsource (lib "EE209_SchLib") (part "TestPoint"))
    )
    (comp (ref "TP5")
      (value "5003")
      (footprint "EE209_PcbLib:TP_TH")
      (description "Test Point, Orange, 1-Pin THD, RoHS")
      (libsource (lib "EE209_SchLib") (part "TestPoint"))
    )
    (comp (ref "TP6")
      (value "5003")
      (footprint "EE209_PcbLib:TP_TH")
      (description "Test Point, Orange, 1-Pin THD, RoHS")
      (libsource (lib "EE209_SchLib") (part "TestPoint"))
    )
    (comp (ref "TP7")
      (value "5003")
      (footprint "EE209_PcbLib:TP_TH")
      (description "Test Point, Orange, 1-Pin THD, RoHS")
      (libsource (lib "EE209_SchLib") (part "TestPoint"))
    )
    (comp (ref "TP8")
      (value "5003")
      (footprint "EE209_PcbLib:TP_TH")
      (description "Test Point, Orange, 1-Pin THD, RoHS")
      (libsource (lib "EE209_SchLib") (part "TestPoint"))
    )
    (comp (ref "TP9")
      (value "5003")
      (footprint "EE209_PcbLib:TP_TH")
      (description "Test Point, Orange, 1-Pin THD, RoHS")
      (libsource (lib "EE209_SchLib") (part "TestPoint"))
    )
    (comp (ref "TP10")
      (value "5003")
      (footprint "EE209_PcbLib:TP_TH")
      (description "Test Point, Orange, 1-Pin THD, RoHS")
      (libsource (lib "EE209_SchLib") (part "TestPoint"))
    )
    (comp (ref "TP11")
      (value "5003")
      (footprint "EE209_PcbLib:TP_TH")
      (description "Test Point, Orange, 1-Pin THD, RoHS")
      (libsource (lib "EE209_SchLib") (part "TestPoint"))
    )
    (comp (ref "TP12")
      (value "5003")
      (footprint "EE209_PcbLib:TP_TH")
      (description "Test Point, Orange, 1-Pin THD, RoHS")
      (libsource (lib "EE209_SchLib") (part "TestPoint"))
    )
    (comp (ref "TP13")
      (value "5003")
      (footprint "EE209_PcbLib:TP_TH")
      (description "Test Point, Orange, 1-Pin THD, RoHS")
      (libsource (lib "EE209_SchLib") (part "TestPoint"))
    )
    (comp (ref "TP14")
      (value "5003")
      (footprint "EE209_PcbLib:TP_TH")
      (description "Test Point, Orange, 1-Pin THD, RoHS")
      (libsource (lib "EE209_SchLib") (part "TestPoint"))
    )
    (comp (ref "U1")
      (value "ADA4807-4ARUZ-R7")
      (footprint "FP-RU-14-IPC_B")
      (description "IC OPAMP VFB 4 CIRCUIT 14TSSOP")
      (libsource (lib "Altium Content Vault") (part "50bd8b37c8612bc519e28063e0f4054"))
    )
    (comp (ref "U2")
      (value "LTC3260EMSE#TRPBF")
      (footprint "LT-MSE-16-EDP_L")
      (fields (field (name "MANUFACTURER") "Linear Technology"))
      (libsource (lib "Altium Content Vault") (part "LT-LTC3260-MSE-16"))
    )
    (comp (ref "U3")
      (value "UCC27531DBVR")
      (footprint "FP-DBV0006A-IPC_B")
      (description "IC GATE DRVR LOW-SIDE SOT23-6")
      (libsource (lib "Altium Content Vault") (part "16a91a241c20d76ff8c7580b319091c"))
    )
    (comp (ref "U4")
      (value "LD1117S33TR")
      (footprint "SOT-223_L")
      (description "Fixed Low Drop Positive Voltage Regulator, 3.3V, 4-Pin SOT-223, Tape and Reel")
      (libsource (lib "Altium Content Vault") (part "PM-REG-LD1117-SOT4"))
    )
    (comp (ref "U5")
      (value "SN74AUC1G86DCKR")
      (footprint "DCK0005A_N")
      (description "Single 2-Input Exclusive-OR Gate, DCK0005A, LARGE T&R")
      (fields
        (field (name "MANUFACTURER") "Texas Instruments")
        (field (name "GENERIC PART NUMBER") "SN74AUC1G86")
      )
      (libsource (lib "Altium Content Vault") (part "TI-XOR-1-2IN-5"))
    )
    (comp (ref "U6")
      (value "LTC2203CUK#TRPBF")
      (footprint "FP-UK-48-05-08-1704-IPC_C")
      (description "IC ADC 16BIT PIPELINED 48QFN")
      (libsource (lib "Altium Content Vault") (part "dbb119f1cd0a03bf6852efc88f5839a"))
    )
    (comp (ref "U7")
      (value "MIC5501-3.0YM5-TR")
      (footprint "FP-SOT23-5LD-PL-1-MFG")
      (description "IC REG LINEAR 3V 300MA SOT23-5")
      (libsource (lib "Altium Content Vault") (part "49efecb8457b62bbb278fcbf558b656"))
    )
    (comp (ref "U8")
      (value "74VCX245BQX")
      (footprint "QFN21P50_450X250X80L40X24T305X105N")
      (description "IC TXRX NON-INVERT 3.6V 20-DQFN")
      (libsource (lib "74VCX245BQX") (part "74VCX245BQX"))
    )
    (comp (ref "U9")
      (value "CMOD_A7_35")
      (footprint "PCBComponent_1 - duplicate")
      (libsource (lib "CMOD_A7_35") (part "CMOD_A7_35"))
    )
    (comp (ref "U10")
      (value "LTC6363IMS8-0.5#PBF")
      (footprint "FP-MS8-8-05-08-1660-IPC_A")
      (description "IC OPAMP DIFF 1 CIRCUIT 8MSOP")
      (libsource (lib "Altium Content Vault") (part "10715e18a46888876e82d6eaefdc557"))
    )
    (comp (ref "U11")
      (value "MIC5365-3.3YD5-TR")
      (footprint "FP-TSOT-5LD-PL-1-IPC_C")
      (description "IC REG LIN 3.3V 150MA TSOT23-5")
      (libsource (lib "Altium Content Vault") (part "9cd1ec1f75c858dde3b53bd37fde33b"))
    )
    (comp (ref "U12")
      (value "74VCX245BQX")
      (footprint "QFN21P50_450X250X80L40X24T305X105N")
      (description "IC TXRX NON-INVERT 3.6V 20-DQFN")
      (libsource (lib "74VCX245BQX") (part "74VCX245BQX"))
    )
    (comp (ref "W1")
      (value "Jumper")
      (footprint "FP-M20-9990246-MFG")
      (description "Jumper Wire")
      (fields (field (name "PUBLISHER") "Altium Limited"))
      (libsource (lib "Miscellaneous Devices") (part "Jumper"))
    )
    (comp (ref "W2")
      (value "Jumper")
      (footprint "FP-M20-9990246-MFG")
      (description "Jumper Wire")
      (fields (field (name "PUBLISHER") "Altium Limited"))
      (libsource (lib "Miscellaneous Devices") (part "Jumper"))
    )
    (comp (ref "W3")
      (value "Jumper")
      (footprint "FP-M20-9990246-MFG")
      (description "Jumper Wire")
      (fields (field (name "PUBLISHER") "Altium Limited"))
      (libsource (lib "Miscellaneous Devices") (part "Jumper"))
    )
    (comp (ref "W4")
      (value "Jumper")
      (footprint "FP-M20-9990246-MFG")
      (description "Jumper Wire")
      (fields (field (name "PUBLISHER") "Altium Limited"))
      (libsource (lib "Miscellaneous Devices") (part "Jumper"))
    )
    (comp (ref "W5")
      (value "Jumper")
      (footprint "FP-M20-9990246-MFG")
      (description "Jumper Wire")
      (fields (field (name "PUBLISHER") "Altium Limited"))
      (libsource (lib "Miscellaneous Devices") (part "Jumper"))
    )
    (comp (ref "X1")
      (value "8 MHz")
      (footprint "FP-ASFL1-MFG")
      (description "Quartz_SX-6 (SMD06035C4)")
      (fields (field (name "Comment") "Quartz"))
      (libsource (lib "lcd_lib") (part "Quartz_SX-6"))
    )
  )
  (nets
    (net (code "1") (name "/+5V") (class "Default")
      (node (ref "C3") (pin "1") (pinfunction "1_1") (pintype "passive"))
      (node (ref "C4") (pin "1") (pinfunction "1_1") (pintype "passive"))
      (node (ref "C5") (pin "1") (pinfunction "1_1") (pintype "passive"))
      (node (ref "C63") (pin "1") (pinfunction "1_1") (pintype "passive"))
      (node (ref "C64") (pin "1") (pinfunction "1_1") (pintype "passive"))
      (node (ref "C65") (pin "1") (pinfunction "1_1") (pintype "passive"))
      (node (ref "P3") (pin "1") (pinfunction "1_1") (pintype "passive"))
      (node (ref "P3") (pin "3") (pinfunction "3_3") (pintype "passive"))
      (node (ref "TP3") (pin "1") (pinfunction "1_1") (pintype "passive"))
      (node (ref "U1") (pin "4") (pinfunction "+VS_4") (pintype "power_in"))
      (node (ref "U10") (pin "3") (pinfunction "V+_3") (pintype "power_in"))
      (node (ref "W1") (pin "2") (pinfunction "C2_2") (pintype "passive"))
    )
    (net (code "2") (name "/-5V") (class "Default")
      (node (ref "C10") (pin "1") (pinfunction "1_1") (pintype "passive"))
      (node (ref "C11") (pin "1") (pinfunction "1_1") (pintype "passive"))
      (node (ref "C9") (pin "1") (pinfunction "1_1") (pintype "passive"))
      (node (ref "P3") (pin "2") (pinfunction "2_2") (pintype "passive"))
      (node (ref "P3") (pin "4") (pinfunction "4_4") (pintype "passive"))
      (node (ref "TP5") (pin "1") (pinfunction "1_1") (pintype "passive"))
      (node (ref "U1") (pin "11") (pinfunction "-VS_11") (pintype "power_in"))
      (node (ref "W2") (pin "2") (pinfunction "C2_2") (pintype "passive"))
    )
    (net (code "3") (name "/ADC_AVDD") (class "Default")
      (node (ref "C69") (pin "2") (pinfunction "2_2") (pintype "passive"))
      (node (ref "C70") (pin "1") (pinfunction "1_1") (pintype "passive"))
      (node (ref "C71") (pin "1") (pinfunction "1_1") (pintype "passive"))
      (node (ref "C72") (pin "1") (pinfunction "1_1") (pintype "passive"))
      (node (ref "C73") (pin "1") (pinfunction "1_1") (pintype "passive"))
      (node (ref "C74") (pin "1") (pinfunction "1_1") (pintype "passive"))
      (node (ref "P7") (pin "1") (pinfunction "1_1") (pintype "passive"))
      (node (ref "P7") (pin "3") (pinfunction "3_3") (pintype "passive"))
      (node (ref "R31") (pin "2") (pinfunction "2_2") (pintype "passive"))
      (node (ref "R32") (pin "2") (pinfunction "2_2") (pintype "passive"))
      (node (ref "R34") (pin "2") (pinfunction "2_2") (pintype "passive"))
      (node (ref "R58") (pin "2") (pinfunction "2_2") (pintype "passive"))
      (node (ref "TP13") (pin "1") (pinfunction "1_1") (pintype "passive"))
      (node (ref "U6") (pin "12") (pinfunction "VDD_12") (pintype "power_in"))
      (node (ref "U6") (pin "13") (pinfunction "VDD_13") (pintype "power_in"))
      (node (ref "U6") (pin "14") (pinfunction "VDD_14") (pintype "power_in"))
      (node (ref "U6") (pin "3") (pinfunction "VDD_3") (pintype "power_in"))
      (node (ref "U6") (pin "4") (pinfunction "VDD_4") (pintype "power_in"))
      (node (ref "W4") (pin "2") (pinfunction "C2_2") (pintype "passive"))
    )
    (net (code "4") (name "/ADC_CLKIN") (class "Default")
      (node (ref "R49") (pin "1") (pinfunction "1_1") (pintype "passive"))
      (node (ref "U9") (pin "29") (pinfunction "D29_29") (pintype "passive"))
    )
    (net (code "5") (name "/ADC_CLKOUT") (class "Default")
      (node (ref "U5") (pin "2") (pinfunction "B_2") (pintype "input"))
      (node (ref "U6") (pin "30") (pinfunction "CLKOUT+_30") (pintype "passive"))
    )
    (net (code "6") (name "/ADC_CLKOUT_F") (class "Default")
      (node (ref "R35") (pin "1") (pinfunction "1_1") (pintype "passive"))
      (node (ref "U5") (pin "4") (pinfunction "Y_4") (pintype "output"))
    )
    (net (code "7") (name "/ADC_DITH") (class "Default")
      (node (ref "J6") (pin "2") (pinfunction "2_2") (pintype "passive"))
      (node (ref "U6") (pin "17") (pinfunction "DITH_17") (pintype "passive"))
    )
    (net (code "8") (name "/ADC_MODE") (class "Default")
      (node (ref "R31") (pin "1") (pinfunction "1_1") (pintype "passive"))
      (node (ref "R33") (pin "2") (pinfunction "2_2") (pintype "passive"))
      (node (ref "U6") (pin "45") (pinfunction "MODE_45") (pintype "output"))
    )
    (net (code "9") (name "/ADC_OVDD") (class "Default")
      (node (ref "C44") (pin "2") (pinfunction "2_2") (pintype "passive"))
      (node (ref "C45") (pin "1") (pinfunction "1_1") (pintype "passive"))
      (node (ref "C46") (pin "1") (pinfunction "1_1") (pintype "passive"))
      (node (ref "C47") (pin "1") (pinfunction "1_1") (pintype "passive"))
      (node (ref "C48") (pin "1") (pinfunction "1_1") (pintype "passive"))
      (node (ref "C50") (pin "1") (pinfunction "1_1") (pintype "passive"))
      (node (ref "J7") (pin "1") (pinfunction "1_1") (pintype "passive"))
      (node (ref "P7") (pin "2") (pinfunction "2_2") (pintype "passive"))
      (node (ref "P7") (pin "4") (pinfunction "4_4") (pintype "passive"))
      (node (ref "TP14") (pin "1") (pinfunction "1_1") (pintype "passive"))
      (node (ref "U12") (pin "20") (pinfunction "VCC_20") (pintype "passive"))
      (node (ref "U6") (pin "24") (pinfunction "OVDD_24") (pintype "power_in"))
      (node (ref "U6") (pin "25") (pinfunction "OVDD_25") (pintype "power_in"))
      (node (ref "U6") (pin "36") (pinfunction "OVDD_36") (pintype "power_in"))
      (node (ref "U6") (pin "37") (pinfunction "OVDD_37") (pintype "power_in"))
      (node (ref "U8") (pin "20") (pinfunction "VCC_20") (pintype "passive"))
      (node (ref "W5") (pin "2") (pinfunction "C2_2") (pintype "passive"))
    )
    (net (code "10") (name "/ADC_RAND") (class "Default")
      (node (ref "J5") (pin "2") (pinfunction "2_2") (pintype "passive"))
      (node (ref "U6") (pin "46") (pinfunction "RAND_46") (pintype "output"))
    )
    (net (code "11") (name "/ADC_VCM") (class "Default")
      (node (ref "C49") (pin "1") (pinfunction "1_1") (pintype "passive"))
      (node (ref "C55") (pin "1") (pinfunction "1_1") (pintype "passive"))
      (node (ref "R40") (pin "1") (pinfunction "1_1") (pintype "passive"))
      (node (ref "U6") (pin "2") (pinfunction "VCM_2") (pintype "passive"))
    )
    (net (code "12") (name "/ENC") (class "Default")
      (node (ref "DD1") (pin "10") (pinfunction "PA0_10") (pintype "passive"))
      (node (ref "R29") (pin "2") (pinfunction "2_2") (pintype "passive"))
    )
    (net (code "13") (name "/LASER_DAC") (class "Default")
      (node (ref "DD1") (pin "15") (pinfunction "PA5_15") (pintype "passive"))
      (node (ref "R27") (pin "1") (pinfunction "1_1") (pintype "passive"))
      (node (ref "TP7") (pin "1") (pinfunction "1_1") (pintype "passive"))
    )
    (net (code "14") (name "/LASER_PULSE") (class "Default")
      (node (ref "DD1") (pin "17") (pinfunction "PA7_17") (pintype "passive"))
      (node (ref "R20") (pin "2") (pinfunction "2_2") (pintype "passive"))
      (node (ref "R24") (pin "2") (pinfunction "2_2") (pintype "passive"))
      (node (ref "R60") (pin "2") (pinfunction "2_2") (pintype "passive"))
      (node (ref "TP8") (pin "1") (pinfunction "1_1") (pintype "passive"))
    )
    (net (code "15") (name "/LTC3260_ADJ+") (class "Default")
      (node (ref "R1") (pin "1") (pinfunction "1_1") (pintype "passive"))
      (node (ref "R2") (pin "2") (pinfunction "2_2") (pintype "passive"))
      (node (ref "U2") (pin "15") (pinfunction "ADJ+_15") (pintype "input"))
    )
    (net (code "16") (name "/LTC3260_ADJ-") (class "Default")
      (node (ref "R3") (pin "1") (pinfunction "1_1") (pintype "passive"))
      (node (ref "R5") (pin "2") (pinfunction "2_2") (pintype "passive"))
      (node (ref "U2") (pin "4") (pinfunction "ADJ-_4") (pintype "input"))
    )
    (net (code "17") (name "/LTC3260_BYP+") (class "Default")
      (node (ref "C7") (pin "2") (pinfunction "2_2") (pintype "passive"))
      (node (ref "U2") (pin "16") (pinfunction "BYP+_16") (pintype "passive"))
    )
    (net (code "18") (name "/LTC3260_BYP-") (class "Default")
      (node (ref "C8") (pin "2") (pinfunction "2_2") (pintype "passive"))
      (node (ref "U2") (pin "3") (pinfunction "BYP-_3") (pintype "passive"))
    )
    (net (code "19") (name "/LTC3260_LDO+") (class "Default")
      (node (ref "C1") (pin "1") (pinfunction "1_1") (pintype "passive"))
      (node (ref "R1") (pin "2") (pinfunction "2_2") (pintype "passive"))
      (node (ref "U2") (pin "12") (pinfunction "LDO+_12") (pintype "power_in"))
      (node (ref "W1") (pin "1") (pinfunction "C1_1") (pintype "passive"))
    )
    (net (code "20") (name "/LTC3260_LDO-") (class "Default")
      (node (ref "C17") (pin "1") (pinfunction "1_1") (pintype "passive"))
      (node (ref "R5") (pin "1") (pinfunction "1_1") (pintype "passive"))
      (node (ref "U2") (pin "5") (pinfunction "LDO-_5") (pintype "power_in"))
      (node (ref "W2") (pin "1") (pinfunction "C1_1") (pintype "passive"))
    )
    (net (code "21") (name "/NRST") (class "Default")
      (node (ref "C35") (pin "1") (pinfunction "1_1") (pintype "passive"))
      (node (ref "DD1") (pin "7") (pinfunction "NRES_7") (pintype "passive"))
      (node (ref "R30") (pin "2") (pinfunction "2_2") (pintype "passive"))
    )
    (net (code "22") (name "/OPAMP_OUT") (class "Default")
      (node (ref "C59") (pin "1") (pinfunction "1_1") (pintype "passive"))
      (node (ref "R44") (pin "1") (pinfunction "1_1") (pintype "passive"))
      (node (ref "R8") (pin "2") (pinfunction "2_2") (pintype "passive"))
      (node (ref "TP4") (pin "1") (pinfunction "1_1") (pintype "passive"))
    )
    (net (code "23") (name "/RX") (class "Default")
      (node (ref "DD1") (pin "40") (pinfunction "PB4_40") (pintype "passive"))
      (node (ref "P6") (pin "4") (pinfunction "4_4") (pintype "passive"))
    )
    (net (code "24") (name "/SWCLK") (class "Default")
      (node (ref "DD1") (pin "37") (pinfunction "PA14/SWCLK_37") (pintype "passive"))
      (node (ref "P6") (pin "2") (pinfunction "2_2") (pintype "passive"))
    )
    (net (code "25") (name "/SWDIO") (class "Default")
      (node (ref "DD1") (pin "34") (pinfunction "PA13/SWDIO_34") (pintype "passive"))
      (node (ref "P6") (pin "1") (pinfunction "1_1") (pintype "passive"))
    )
    (net (code "26") (name "/TX") (class "Default")
      (node (ref "DD1") (pin "39") (pinfunction "PB3_39") (pintype "passive"))
      (node (ref "P6") (pin "5") (pinfunction "5_5") (pintype "passive"))
    )
    (net (code "27") (name "/UCC_ENABLE") (class "Default")
      (node (ref "DD1") (pin "31") (pinfunction "PA10_31") (pintype "passive"))
      (node (ref "R26") (pin "1") (pinfunction "1_1") (pintype "passive"))
    )
    (net (code "28") (name "3V3") (class "Default")
      (node (ref "C40") (pin "1") (pinfunction "1_1") (pintype "passive"))
      (node (ref "C41") (pin "1") (pinfunction "1_1") (pintype "passive"))
      (node (ref "C42") (pin "1") (pinfunction "1_1") (pintype "passive"))
      (node (ref "C43") (pin "1") (pinfunction "1_1") (pintype "passive"))
      (node (ref "DD1") (pin "1") (pinfunction "VBAT_1") (pintype "passive"))
      (node (ref "DD1") (pin "24") (pinfunction "VDD_24") (pintype "passive"))
      (node (ref "DD1") (pin "36") (pinfunction "VDD_36") (pintype "passive"))
      (node (ref "DD1") (pin "48") (pinfunction "VDD_48") (pintype "passive"))
      (node (ref "DD1") (pin "9") (pinfunction "VDDA_9") (pintype "passive"))
      (node (ref "P2") (pin "1") (pinfunction "1_1") (pintype "passive"))
      (node (ref "P2") (pin "2") (pinfunction "2_2") (pintype "passive"))
      (node (ref "R29") (pin "1") (pinfunction "1_1") (pintype "passive"))
      (node (ref "R30") (pin "1") (pinfunction "1_1") (pintype "passive"))
      (node (ref "TP2") (pin "1") (pinfunction "1_1") (pintype "passive"))
      (node (ref "W3") (pin "2") (pinfunction "C2_2") (pintype "passive"))
    )
    (net (code "29") (name "GND") (class "Default")
      (node (ref "C1") (pin "2") (pinfunction "2_2") (pintype "passive"))
      (node (ref "C10") (pin "2") (pinfunction "2_2") (pintype "passive"))
      (node (ref "C11") (pin "2") (pinfunction "2_2") (pintype "passive"))
      (node (ref "C17") (pin "2") (pinfunction "2_2") (pintype "passive"))
      (node (ref "C2") (pin "2") (pinfunction "2_2") (pintype "passive"))
      (node (ref "C20") (pin "2") (pinfunction "2_2") (pintype "passive"))
      (node (ref "C22") (pin "2") (pinfunction "2_2") (pintype "passive"))
      (node (ref "C23") (pin "2") (pinfunction "2_2") (pintype "passive"))
      (node (ref "C24") (pin "1") (pinfunction "1_1") (pintype "passive"))
      (node (ref "C29") (pin "1") (pinfunction "1_1") (pintype "passive"))
      (node (ref "C3") (pin "2") (pinfunction "2_2") (pintype "passive"))
      (node (ref "C30") (pin "1") (pinfunction "1_1") (pintype "passive"))
      (node (ref "C31") (pin "2") (pinfunction "2_2") (pintype "passive"))
      (node (ref "C32") (pin "2") (pinfunction "2_2") (pintype "passive"))
      (node (ref "C33") (pin "1") (pinfunction "1_1") (pintype "passive"))
      (node (ref "C34") (pin "1") (pinfunction "1_1") (pintype "passive"))
      (node (ref "C35") (pin "2") (pinfunction "2_2") (pintype "passive"))
      (node (ref "C36") (pin "1") (pinfunction "1_1") (pintype "passive"))
      (node (ref "C37") (pin "2") (pinfunction "2_2") (pintype "passive"))
      (node (ref "C38") (pin "2") (pinfunction "2_2") (pintype "passive"))
      (node (ref "C39") (pin "2") (pinfunction "2_2") (pintype "passive"))
      (node (ref "C4") (pin "2") (pinfunction "2_2") (pintype "passive"))
      (node (ref "C40") (pin "2") (pinfunction "2_2") (pintype "passive"))
      (node (ref "C41") (pin "2") (pinfunction "2_2") (pintype "passive"))
      (node (ref "C42") (pin "2") (pinfunction "2_2") (pintype "passive"))
      (node (ref "C43") (pin "2") (pinfunction "2_2") (pintype "passive"))
      (node (ref "C44") (pin "1") (pinfunction "1_1") (pintype "passive"))
      (node (ref "C45") (pin "2") (pinfunction "2_2") (pintype "passive"))
      (node (ref "C46") (pin "2") (pinfunction "2_2") (pintype "passive"))
      (node (ref "C47") (pin "2") (pinfunction "2_2") (pintype "passive"))
      (node (ref "C48") (pin "2") (pinfunction "2_2") (pintype "passive"))
      (node (ref "C49") (pin "2") (pinfunction "2_2") (pintype "passive"))
      (node (ref "C5") (pin "2") (pinfunction "2_2") (pintype "passive"))
      (node (ref "C50") (pin "2") (pinfunction "2_2") (pintype "passive"))
      (node (ref "C51") (pin "1") (pinfunction "1_1") (pintype "passive"))
      (node (ref "C52") (pin "1") (pinfunction "1_1") (pintype "passive"))
      (node (ref "C54") (pin "1") (pinfunction "1_1") (pintype "passive"))
      (node (ref "C55") (pin "2") (pinfunction "2_2") (pintype "passive"))
      (node (ref "C57") (pin "1") (pinfunction "1_1") (pintype "passive"))
      (node (ref "C58") (pin "1") (pinfunction "1_1") (pintype "passive"))
      (node (ref "C59") (pin "2") (pinfunction "2_2") (pintype "passive"))
      (node (ref "C6") (pin "2") (pinfunction "2_2") (pintype "passive"))
      (node (ref "C60") (pin "2") (pinfunction "2_2") (pintype "passive"))
      (node (ref "C63") (pin "2") (pinfunction "2_2") (pintype "passive"))
      (node (ref "C64") (pin "2") (pinfunction "2_2") (pintype "passive"))
      (node (ref "C65") (pin "2") (pinfunction "2_2") (pintype "passive"))
      (node (ref "C69") (pin "1") (pinfunction "1_1") (pintype "passive"))
      (node (ref "C7") (pin "1") (pinfunction "1_1") (pintype "passive"))
      (node (ref "C70") (pin "2") (pinfunction "2_2") (pintype "passive"))
      (node (ref "C71") (pin "2") (pinfunction "2_2") (pintype "passive"))
      (node (ref "C72") (pin "2") (pinfunction "2_2") (pintype "passive"))
      (node (ref "C73") (pin "2") (pinfunction "2_2") (pintype "passive"))
      (node (ref "C74") (pin "2") (pinfunction "2_2") (pintype "passive"))
      (node (ref "C8") (pin "1") (pinfunction "1_1") (pintype "passive"))
      (node (ref "C9") (pin "2") (pinfunction "2_2") (pintype "passive"))
      (node (ref "D2") (pin "2") (pinfunction "K_2") (pintype "passive"))
      (node (ref "DA1") (pin "2") (pinfunction "GND_2") (pintype "power_in"))
      (node (ref "DD1") (pin "23") (pinfunction "VSS_23") (pintype "passive"))
      (node (ref "DD1") (pin "35") (pinfunction "VSS_35") (pintype "passive"))
      (node (ref "DD1") (pin "44") (pinfunction "BOOT0_44") (pintype "passive"))
      (node (ref "DD1") (pin "47") (pinfunction "VSS_47") (pintype "passive"))
      (node (ref "DD1") (pin "8") (pinfunction "VSSA_8") (pintype "passive"))
      (node (ref "J1") (pin "2") (pinfunction "GND_2") (pintype "power_in"))
      (node (ref "J1") (pin "3") (pinfunction "GND_3") (pintype "power_in"))
      (node (ref "J2") (pin "2") (pinfunction "GND_2") (pintype "power_in"))
      (node (ref "J2") (pin "3") (pinfunction "GND_3") (pintype "power_in"))
      (node (ref "J3") (pin "2") (pinfunction "GND_2") (pintype "power_in"))
      (node (ref "J3") (pin "3") (pinfunction "GND_3") (pintype "power_in"))
      (node (ref "J4") (pin "2") (pinfunction "GND_2") (pintype "power_in"))
      (node (ref "J4") (pin "3") (pinfunction "GND_3") (pintype "power_in"))
      (node (ref "J5") (pin "3") (pinfunction "3_3") (pintype "passive"))
      (node (ref "J6") (pin "3") (pinfunction "3_3") (pintype "passive"))
      (node (ref "J7") (pin "3") (pinfunction "3_3") (pintype "passive"))
      (node (ref "J8") (pin "2") (pinfunction "GND_2") (pintype "power_in"))
      (node (ref "J8") (pin "3") (pinfunction "GND_3") (pintype "power_in"))
      (node (ref "J9") (pin "2") (pinfunction "GND_2") (pintype "power_in"))
      (node (ref "J9") (pin "3") (pinfunction "GND_3") (pintype "power_in"))
      (node (ref "P1") (pin "2") (pinfunction "Y_2") (pintype "passive"))
      (node (ref "P4") (pin "1") (pinfunction "1_1") (pintype "passive"))
      (node (ref "P4") (pin "2") (pinfunction "2_2") (pintype "passive"))
      (node (ref "P4") (pin "3") (pinfunction "3_3") (pintype "passive"))
      (node (ref "P4") (pin "4") (pinfunction "4_4") (pintype "passive"))
      (node (ref "P4") (pin "5") (pinfunction "5_5") (pintype "passive"))
      (node (ref "P4") (pin "6") (pinfunction "6_6") (pintype "passive"))
      (node (ref "P4") (pin "7") (pinfunction "7_7") (pintype "passive"))
      (node (ref "P4") (pin "8") (pinfunction "8_8") (pintype "passive"))
      (node (ref "P6") (pin "3") (pinfunction "3_3") (pintype "passive"))
      (node (ref "Q1") (pin "3") (pinfunction "SOURCE_3") (pintype "passive"))
      (node (ref "R10") (pin "1") (pinfunction "1_1") (pintype "passive"))
      (node (ref "R12") (pin "1") (pinfunction "1_1") (pintype "passive"))
      (node (ref "R2") (pin "1") (pinfunction "1_1") (pintype "passive"))
      (node (ref "R24") (pin "1") (pinfunction "1_1") (pintype "passive"))
      (node (ref "R25") (pin "1") (pinfunction "1_1") (pintype "passive"))
      (node (ref "R28") (pin "1") (pinfunction "1_1") (pintype "passive"))
      (node (ref "R3") (pin "2") (pinfunction "2_2") (pintype "passive"))
      (node (ref "R33") (pin "1") (pinfunction "1_1") (pintype "passive"))
      (node (ref "R4") (pin "1") (pinfunction "1_1") (pintype "passive"))
      (node (ref "R9") (pin "1") (pinfunction "1_1") (pintype "passive"))
      (node (ref "TP11") (pin "1") (pinfunction "1_1") (pintype "passive"))
      (node (ref "TP12") (pin "1") (pinfunction "1_1") (pintype "passive"))
      (node (ref "U10") (pin "1") (pinfunction "-IN_1") (pintype "tri_state"))
      (node (ref "U10") (pin "6") (pinfunction "V-_6") (pintype "power_in"))
      (node (ref "U11") (pin "2") (pinfunction "GND_2") (pintype "power_in"))
      (node (ref "U12") (pin "1") (pinfunction "T/~{R}_1") (pintype "passive"))
      (node (ref "U12") (pin "10") (pinfunction "GND_10") (pintype "passive"))
      (node (ref "U12") (pin "19") (pinfunction "~{OE}_19") (pintype "passive"))
      (node (ref "U2") (pin "14") (pinfunction "MODE_14") (pintype "input"))
      (node (ref "U2") (pin "17") (pinfunction "EP_17") (pintype "power_in"))
      (node (ref "U3") (pin "4") (pinfunction "GND_4") (pintype "power_in"))
      (node (ref "U4") (pin "1") (pinfunction "GND_1") (pintype "power_in"))
      (node (ref "U6") (pin "11") (pinfunction "GND_11") (pintype "power_in"))
      (node (ref "U6") (pin "15") (pinfunction "GND_15") (pintype "power_in"))
      (node (ref "U6") (pin "16") (pinfunction "SHDN_16") (pintype "input"))
      (node (ref "U6") (pin "23") (pinfunction "OGND_23") (pintype "power_in"))
      (node (ref "U6") (pin "31") (pinfunction "OGND_31") (pintype "power_in"))
      (node (ref "U6") (pin "38") (pinfunction "OGND_38") (pintype "power_in"))
      (node (ref "U6") (pin "44") (pinfunction "~{OE}_44") (pintype "output"))
      (node (ref "U6") (pin "47") (pinfunction "PGA_47") (pintype "input"))
      (node (ref "U6") (pin "48") (pinfunction "GND_48") (pintype "power_in"))
      (node (ref "U6") (pin "49") (pinfunction "EP_49") (pintype "power_in"))
      (node (ref "U6") (pin "5") (pinfunction "GND_5") (pintype "power_in"))
      (node (ref "U6") (pin "8") (pinfunction "GND_8") (pintype "power_in"))
      (node (ref "U6") (pin "9") (pinfunction "GND_9") (pintype "power_in"))
      (node (ref "U7") (pin "2") (pinfunction "GND_2") (pintype "power_in"))
      (node (ref "U8") (pin "1") (pinfunction "T/~{R}_1") (pintype "passive"))
      (node (ref "U8") (pin "10") (pinfunction "GND_10") (pintype "passive"))
      (node (ref "U8") (pin "19") (pinfunction "~{OE}_19") (pintype "passive"))
      (node (ref "U9") (pin "25") (pinfunction "GND_25") (pintype "passive"))
    )
    (net (code "30") (name "Net-(C20-Pad1)") (class "Default")
      (node (ref "C20") (pin "1") (pinfunction "1_1") (pintype "passive"))
      (node (ref "R15") (pin "2") (pinfunction "2_2") (pintype "passive"))
    )
    (net (code "31") (name "Net-(C22-Pad1)") (class "Default")
      (node (ref "C22") (pin "1") (pinfunction "1_1") (pintype "passive"))
      (node (ref "R16") (pin "2") (pinfunction "2_2") (pintype "passive"))
    )
    (net (code "32") (name "Net-(C23-Pad1)") (class "Default")
      (node (ref "C23") (pin "1") (pinfunction "1_1") (pintype "passive"))
      (node (ref "R17") (pin "2") (pinfunction "2_2") (pintype "passive"))
    )
    (net (code "33") (name "Net-(C54-Pad2)") (class "Default")
      (node (ref "C54") (pin "2") (pinfunction "2_2") (pintype "passive"))
      (node (ref "C56") (pin "1") (pinfunction "1_1") (pintype "passive"))
      (node (ref "R42") (pin "1") (pinfunction "1_1") (pintype "passive"))
      (node (ref "R46") (pin "1") (pinfunction "1_1") (pintype "passive"))
    )
    (net (code "34") (name "Net-(C56-Pad2)") (class "Default")
      (node (ref "C56") (pin "2") (pinfunction "2_2") (pintype "passive"))
      (node (ref "C60") (pin "1") (pinfunction "1_1") (pintype "passive"))
      (node (ref "R48") (pin "1") (pinfunction "1_1") (pintype "passive"))
      (node (ref "R52") (pin "1") (pinfunction "1_1") (pintype "passive"))
    )
    (net (code "35") (name "Net-(D1-A)") (class "Default")
      (node (ref "D1") (pin "1") (pinfunction "A_1") (pintype "passive"))
      (node (ref "R21") (pin "1") (pinfunction "1_1") (pintype "passive"))
      (node (ref "R25") (pin "2") (pinfunction "2_2") (pintype "passive"))
    )
    (net (code "36") (name "Net-(D1-K)") (class "Default")
      (node (ref "C25") (pin "1") (pinfunction "1_1") (pintype "passive"))
      (node (ref "D1") (pin "2") (pinfunction "K_2") (pintype "passive"))
      (node (ref "D2") (pin "1") (pinfunction "A_1") (pintype "passive"))
      (node (ref "TP9") (pin "1") (pinfunction "1_1") (pintype "passive"))
    )
    (net (code "37") (name "Net-(D3-A)") (class "Default")
      (node (ref "D3") (pin "1") (pinfunction "A_1") (pintype "passive"))
      (node (ref "DA1") (pin "1") (pinfunction "SW_1") (pintype "open_collector"))
      (node (ref "L3") (pin "2") (pinfunction "2_2") (pintype "passive"))
    )
    (net (code "38") (name "Net-(DA1-EN)") (class "Default")
      (node (ref "C30") (pin "2") (pinfunction "2_2") (pintype "passive"))
      (node (ref "DA1") (pin "4") (pinfunction "EN_4") (pintype "power_in"))
      (node (ref "DA1") (pin "5") (pinfunction "VIN_5") (pintype "passive"))
      (node (ref "L2") (pin "1") (pinfunction "1_1") (pintype "passive"))
      (node (ref "L3") (pin "1") (pinfunction "1_1") (pintype "passive"))
    )
    (net (code "39") (name "Net-(DA1-FB)") (class "Default")
      (node (ref "DA1") (pin "3") (pinfunction "FB_3") (pintype "power_in"))
      (node (ref "R22") (pin "1") (pinfunction "1_1") (pintype "passive"))
      (node (ref "R27") (pin "2") (pinfunction "2_2") (pintype "passive"))
      (node (ref "R28") (pin "2") (pinfunction "2_2") (pintype "passive"))
    )
    (net (code "40") (name "Net-(DD1-PF0{slash}OSC_IN)") (class "Default")
      (node (ref "C34") (pin "2") (pinfunction "2_2") (pintype "passive"))
      (node (ref "DD1") (pin "5") (pinfunction "PF0/OSC_IN_5") (pintype "passive"))
      (node (ref "X1") (pin "3") (pinfunction "3_3") (pintype "passive"))
    )
    (net (code "41") (name "Net-(DD1-PF0{slash}OSC_OUT)") (class "Default")
      (node (ref "C33") (pin "2") (pinfunction "2_2") (pintype "passive"))
      (node (ref "DD1") (pin "6") (pinfunction "PF0/OSC_OUT_6") (pintype "passive"))
      (node (ref "X1") (pin "1") (pinfunction "1_1") (pintype "passive"))
    )
    (net (code "42") (name "Net-(J1-SIG)") (class "Default")
      (node (ref "J1") (pin "1") (pinfunction "SIG_1") (pintype "passive"))
      (node (ref "R21") (pin "2") (pinfunction "2_2") (pintype "passive"))
    )
    (net (code "43") (name "Net-(J2-SIG)") (class "Default")
      (node (ref "C12") (pin "1") (pinfunction "1_1") (pintype "passive"))
      (node (ref "J2") (pin "1") (pinfunction "SIG_1") (pintype "input"))
    )
    (net (code "44") (name "Net-(J3-SIG)") (class "Default")
      (node (ref "C13") (pin "1") (pinfunction "1_1") (pintype "passive"))
      (node (ref "J3") (pin "1") (pinfunction "SIG_1") (pintype "input"))
    )
    (net (code "45") (name "Net-(J4-SIG)") (class "Default")
      (node (ref "C14") (pin "1") (pinfunction "1_1") (pintype "passive"))
      (node (ref "J4") (pin "1") (pinfunction "SIG_1") (pintype "input"))
    )
    (net (code "46") (name "Net-(J5-Pad1)") (class "Default")
      (node (ref "J5") (pin "1") (pinfunction "1_1") (pintype "passive"))
      (node (ref "R32") (pin "1") (pinfunction "1_1") (pintype "passive"))
    )
    (net (code "47") (name "Net-(J6-Pad1)") (class "Default")
      (node (ref "J6") (pin "1") (pinfunction "1_1") (pintype "passive"))
      (node (ref "R34") (pin "1") (pinfunction "1_1") (pintype "passive"))
    )
    (net (code "48") (name "Net-(J8-SIG)") (class "Default")
      (node (ref "C53") (pin "1") (pinfunction "1_1") (pintype "passive"))
      (node (ref "J8") (pin "1") (pinfunction "SIG_1") (pintype "input"))
    )
    (net (code "49") (name "Net-(J9-SIG)") (class "Default")
      (node (ref "C61") (pin "2") (pinfunction "2_2") (pintype "passive"))
      (node (ref "J9") (pin "1") (pinfunction "SIG_1") (pintype "input"))
    )
    (net (code "50") (name "Net-(P1-X)") (class "Default")
      (node (ref "C16") (pin "1") (pinfunction "1_1") (pintype "passive"))
      (node (ref "P1") (pin "1") (pinfunction "X_1") (pintype "passive"))
      (node (ref "R9") (pin "2") (pinfunction "2_2") (pintype "passive"))
    )
    (net (code "51") (name "Net-(Q1-DRAIN)") (class "Default")
      (node (ref "C25") (pin "2") (pinfunction "2_2") (pintype "passive"))
      (node (ref "Q1") (pin "2") (pinfunction "DRAIN_2") (pintype "passive"))
      (node (ref "R18") (pin "1") (pinfunction "1_1") (pintype "passive"))
      (node (ref "TP10") (pin "1") (pinfunction "1_1") (pintype "passive"))
    )
    (net (code "52") (name "Net-(Q1-GATE)") (class "Default")
      (node (ref "Q1") (pin "1") (pinfunction "GATE_1") (pintype "passive"))
      (node (ref "R19") (pin "1") (pinfunction "1_1") (pintype "passive"))
      (node (ref "R23") (pin "1") (pinfunction "1_1") (pintype "passive"))
    )
    (net (code "53") (name "Net-(U1B-+IN2)") (class "Default")
      (node (ref "C16") (pin "2") (pinfunction "2_2") (pintype "passive"))
      (node (ref "R10") (pin "2") (pinfunction "2_2") (pintype "passive"))
      (node (ref "U1") (pin "5") (pinfunction "+IN2_5") (pintype "tri_state"))
    )
    (net (code "54") (name "Net-(U1B--IN2)") (class "Default")
      (node (ref "C18") (pin "1") (pinfunction "1_1") (pintype "passive"))
      (node (ref "R11") (pin "1") (pinfunction "1_1") (pintype "passive"))
      (node (ref "R15") (pin "1") (pinfunction "1_1") (pintype "passive"))
      (node (ref "U1") (pin "6") (pinfunction "-IN2_6") (pintype "tri_state"))
    )
    (net (code "55") (name "Net-(U1B-VOUT2)") (class "Default")
      (node (ref "C12") (pin "2") (pinfunction "2_2") (pintype "passive"))
      (node (ref "C18") (pin "2") (pinfunction "2_2") (pintype "passive"))
      (node (ref "R11") (pin "2") (pinfunction "2_2") (pintype "passive"))
      (node (ref "R6") (pin "1") (pinfunction "1_1") (pintype "passive"))
      (node (ref "U1") (pin "7") (pinfunction "VOUT2_7") (pintype "passive"))
    )
    (net (code "56") (name "Net-(U1C-+IN3)") (class "Default")
      (node (ref "R6") (pin "2") (pinfunction "2_2") (pintype "passive"))
      (node (ref "U1") (pin "10") (pinfunction "+IN3_10") (pintype "tri_state"))
    )
    (net (code "57") (name "Net-(U1C--IN3)") (class "Default")
      (node (ref "C19") (pin "1") (pinfunction "1_1") (pintype "passive"))
      (node (ref "R13") (pin "1") (pinfunction "1_1") (pintype "passive"))
      (node (ref "R16") (pin "1") (pinfunction "1_1") (pintype "passive"))
      (node (ref "U1") (pin "9") (pinfunction "-IN3_9") (pintype "tri_state"))
    )
    (net (code "58") (name "Net-(U1C-VOUT3)") (class "Default")
      (node (ref "C13") (pin "2") (pinfunction "2_2") (pintype "passive"))
      (node (ref "C19") (pin "2") (pinfunction "2_2") (pintype "passive"))
      (node (ref "R13") (pin "2") (pinfunction "2_2") (pintype "passive"))
      (node (ref "R7") (pin "1") (pinfunction "1_1") (pintype "passive"))
      (node (ref "U1") (pin "8") (pinfunction "VOUT3_8") (pintype "passive"))
    )
    (net (code "59") (name "Net-(U1D-+IN4)") (class "Default")
      (node (ref "R7") (pin "2") (pinfunction "2_2") (pintype "passive"))
      (node (ref "U1") (pin "12") (pinfunction "+IN4_12") (pintype "tri_state"))
    )
    (net (code "60") (name "Net-(U1D--IN4)") (class "Default")
      (node (ref "C21") (pin "1") (pinfunction "1_1") (pintype "passive"))
      (node (ref "R14") (pin "1") (pinfunction "1_1") (pintype "passive"))
      (node (ref "R17") (pin "1") (pinfunction "1_1") (pintype "passive"))
      (node (ref "U1") (pin "13") (pinfunction "-IN4_13") (pintype "tri_state"))
    )
    (net (code "61") (name "Net-(U1D-VOUT4)") (class "Default")
      (node (ref "C14") (pin "2") (pinfunction "2_2") (pintype "passive"))
      (node (ref "C21") (pin "2") (pinfunction "2_2") (pintype "passive"))
      (node (ref "R12") (pin "2") (pinfunction "2_2") (pintype "passive"))
      (node (ref "R14") (pin "2") (pinfunction "2_2") (pintype "passive"))
      (node (ref "R8") (pin "1") (pinfunction "1_1") (pintype "passive"))
      (node (ref "U1") (pin "14") (pinfunction "VOUT4_14") (pintype "passive"))
    )
    (net (code "62") (name "Net-(U2-C+)") (class "Default")
      (node (ref "C15") (pin "1") (pinfunction "1_1") (pintype "passive"))
      (node (ref "U2") (pin "10") (pinfunction "C+_10") (pintype "passive"))
    )
    (net (code "63") (name "Net-(U2-C-)") (class "Default")
      (node (ref "C15") (pin "2") (pinfunction "2_2") (pintype "passive"))
      (node (ref "U2") (pin "7") (pinfunction "C-_7") (pintype "passive"))
    )
    (net (code "64") (name "Net-(U2-RT)") (class "Default")
      (node (ref "R4") (pin "2") (pinfunction "2_2") (pintype "passive"))
      (node (ref "U2") (pin "2") (pinfunction "RT_2") (pintype "passive"))
    )
    (net (code "65") (name "Net-(U2-VOUT)") (class "Default")
      (node (ref "C6") (pin "1") (pinfunction "1_1") (pintype "passive"))
      (node (ref "U2") (pin "6") (pinfunction "VOUT_6") (pintype "power_in"))
    )
    (net (code "66") (name "Net-(U3-EN)") (class "Default")
      (node (ref "R26") (pin "2") (pinfunction "2_2") (pintype "passive"))
      (node (ref "U3") (pin "1") (pinfunction "EN_1") (pintype "input"))
    )
    (net (code "67") (name "Net-(U3-IN)") (class "Default")
      (node (ref "R20") (pin "1") (pinfunction "1_1") (pintype "passive"))
      (node (ref "U3") (pin "2") (pinfunction "IN_2") (pintype "tri_state"))
    )
    (net (code "68") (name "Net-(U3-OUTH)") (class "Default")
      (node (ref "R19") (pin "2") (pinfunction "2_2") (pintype "passive"))
      (node (ref "U3") (pin "6") (pinfunction "OUTH_6") (pintype "passive"))
    )
    (net (code "69") (name "Net-(U3-OUTL)") (class "Default")
      (node (ref "R23") (pin "2") (pinfunction "2_2") (pintype "passive"))
      (node (ref "U3") (pin "5") (pinfunction "OUTL_5") (pintype "passive"))
    )
    (net (code "70") (name "Net-(U3-VDD)") (class "Default")
      (node (ref "C24") (pin "2") (pinfunction "2_2") (pintype "passive"))
      (node (ref "L1") (pin "2") (pinfunction "2_2") (pintype "passive"))
      (node (ref "U3") (pin "3") (pinfunction "VDD_3") (pintype "power_in"))
    )
    (net (code "71") (name "Net-(U5A-A)") (class "Default")
      (node (ref "J7") (pin "2") (pinfunction "2_2") (pintype "passive"))
      (node (ref "U5") (pin "1") (pinfunction "A_1") (pintype "input"))
    )
    (net (code "72") (name "Net-(U6-AIN+)") (class "Default")
      (node (ref "R42") (pin "2") (pinfunction "2_2") (pintype "passive"))
      (node (ref "U6") (pin "6") (pinfunction "AIN+_6") (pintype "passive"))
    )
    (net (code "73") (name "Net-(U6-AIN-)") (class "Default")
      (node (ref "R48") (pin "2") (pinfunction "2_2") (pintype "passive"))
      (node (ref "U6") (pin "7") (pinfunction "AIN-_7") (pintype "passive"))
    )
    (net (code "74") (name "Net-(U6-CLK)") (class "Default")
      (node (ref "R49") (pin "2") (pinfunction "2_2") (pintype "passive"))
      (node (ref "U6") (pin "10") (pinfunction "CLK_10") (pintype "passive"))
    )
    (net (code "75") (name "Net-(U6-D8)") (class "Default")
      (node (ref "U6") (pin "32") (pinfunction "D8_32") (pintype "output"))
      (node (ref "U8") (pin "18") (pinfunction "B_0_18") (pintype "passive"))
    )
    (net (code "76") (name "Net-(U6-D9)") (class "Default")
      (node (ref "U6") (pin "33") (pinfunction "D9_33") (pintype "output"))
      (node (ref "U8") (pin "17") (pinfunction "B_1_17") (pintype "passive"))
    )
    (net (code "77") (name "Net-(U6-D10)") (class "Default")
      (node (ref "U6") (pin "34") (pinfunction "D10_34") (pintype "output"))
      (node (ref "U8") (pin "16") (pinfunction "B_2_16") (pintype "passive"))
    )
    (net (code "78") (name "Net-(U6-D11)") (class "Default")
      (node (ref "U6") (pin "35") (pinfunction "D11_35") (pintype "output"))
      (node (ref "U8") (pin "15") (pinfunction "B_3_15") (pintype "passive"))
    )
    (net (code "79") (name "Net-(U6-D12)") (class "Default")
      (node (ref "U6") (pin "39") (pinfunction "D12_39") (pintype "output"))
      (node (ref "U8") (pin "14") (pinfunction "B_4_14") (pintype "passive"))
    )
    (net (code "80") (name "Net-(U6-D13)") (class "Default")
      (node (ref "U6") (pin "40") (pinfunction "D13_40") (pintype "output"))
      (node (ref "U8") (pin "13") (pinfunction "B_5_13") (pintype "passive"))
    )
    (net (code "81") (name "Net-(U6-D14)") (class "Default")
      (node (ref "U6") (pin "41") (pinfunction "D14_41") (pintype "output"))
      (node (ref "U8") (pin "12") (pinfunction "B_6_12") (pintype "passive"))
    )
    (net (code "82") (name "Net-(U6-D15)") (class "Default")
      (node (ref "U6") (pin "42") (pinfunction "D15_42") (pintype "output"))
      (node (ref "U8") (pin "11") (pinfunction "B_7_11") (pintype "passive"))
    )
    (net (code "83") (name "Net-(U6-SENSE)") (class "Default")
      (node (ref "R58") (pin "1") (pinfunction "1_1") (pintype "passive"))
      (node (ref "U6") (pin "1") (pinfunction "SENSE_1") (pintype "passive"))
    )
    (net (code "84") (name "Net-(U7-VOUT)") (class "Default")
      (node (ref "C52") (pin "2") (pinfunction "2_2") (pintype "passive"))
      (node (ref "U7") (pin "5") (pinfunction "VOUT_5") (pintype "passive"))
      (node (ref "W4") (pin "1") (pinfunction "C1_1") (pintype "passive"))
    )
    (net (code "85") (name "Net-(U8C-A_0)") (class "Default")
      (node (ref "R47") (pin "1") (pinfunction "1_1") (pintype "passive"))
      (node (ref "U8") (pin "2") (pinfunction "A_0_2") (pintype "passive"))
    )
    (net (code "86") (name "Net-(U8C-A_1)") (class "Default")
      (node (ref "R45") (pin "1") (pinfunction "1_1") (pintype "passive"))
      (node (ref "U8") (pin "3") (pinfunction "A_1_3") (pintype "passive"))
    )
    (net (code "87") (name "Net-(U8C-A_2)") (class "Default")
      (node (ref "R43") (pin "1") (pinfunction "1_1") (pintype "passive"))
      (node (ref "U8") (pin "4") (pinfunction "A_2_4") (pintype "passive"))
    )
    (net (code "88") (name "Net-(U8C-A_3)") (class "Default")
      (node (ref "R41") (pin "1") (pinfunction "1_1") (pintype "passive"))
      (node (ref "U8") (pin "5") (pinfunction "A_3_5") (pintype "passive"))
    )
    (net (code "89") (name "Net-(U8C-A_4)") (class "Default")
      (node (ref "R39") (pin "1") (pinfunction "1_1") (pintype "passive"))
      (node (ref "U8") (pin "6") (pinfunction "A_4_6") (pintype "passive"))
    )
    (net (code "90") (name "Net-(U8C-A_5)") (class "Default")
      (node (ref "R38") (pin "1") (pinfunction "1_1") (pintype "passive"))
      (node (ref "U8") (pin "7") (pinfunction "A_5_7") (pintype "passive"))
    )
    (net (code "91") (name "Net-(U8C-A_6)") (class "Default")
      (node (ref "R37") (pin "1") (pinfunction "1_1") (pintype "passive"))
      (node (ref "U8") (pin "8") (pinfunction "A_6_8") (pintype "passive"))
    )
    (net (code "92") (name "Net-(U8C-A_7)") (class "Default")
      (node (ref "R36") (pin "1") (pinfunction "1_1") (pintype "passive"))
      (node (ref "U8") (pin "9") (pinfunction "A_7_9") (pintype "passive"))
    )
    (net (code "93") (name "Net-(U9-A15)") (class "Default")
      (node (ref "R47") (pin "2") (pinfunction "2_2") (pintype "passive"))
      (node (ref "U9") (pin "15") (pinfunction "A15_15") (pintype "passive"))
    )
    (net (code "94") (name "Net-(U9-A16)") (class "Default")
      (node (ref "R50") (pin "2") (pinfunction "2_2") (pintype "passive"))
      (node (ref "U9") (pin "16") (pinfunction "A16_16") (pintype "passive"))
    )
    (net (code "95") (name "Net-(U9-D7)") (class "Default")
      (node (ref "R35") (pin "2") (pinfunction "2_2") (pintype "passive"))
      (node (ref "U9") (pin "7") (pinfunction "D7_7") (pintype "passive"))
    )
    (net (code "96") (name "Net-(U9-D8)") (class "Default")
      (node (ref "R36") (pin "2") (pinfunction "2_2") (pintype "passive"))
      (node (ref "U9") (pin "8") (pinfunction "D8_8") (pintype "passive"))
    )
    (net (code "97") (name "Net-(U9-D9)") (class "Default")
      (node (ref "R37") (pin "2") (pinfunction "2_2") (pintype "passive"))
      (node (ref "U9") (pin "9") (pinfunction "D9_9") (pintype "passive"))
    )
    (net (code "98") (name "Net-(U9-D10)") (class "Default")
      (node (ref "R38") (pin "2") (pinfunction "2_2") (pintype "passive"))
      (node (ref "U9") (pin "10") (pinfunction "D10_10") (pintype "passive"))
    )
    (net (code "99") (name "Net-(U9-D11)") (class "Default")
      (node (ref "R39") (pin "2") (pinfunction "2_2") (pintype "passive"))
      (node (ref "U9") (pin "11") (pinfunction "D11_11") (pintype "passive"))
    )
    (net (code "100") (name "Net-(U9-D12)") (class "Default")
      (node (ref "R41") (pin "2") (pinfunction "2_2") (pintype "passive"))
      (node (ref "U9") (pin "12") (pinfunction "D12_12") (pintype "passive"))
    )
    (net (code "101") (name "Net-(U9-D13)") (class "Default")
      (node (ref "R43") (pin "2") (pinfunction "2_2") (pintype "passive"))
      (node (ref "U9") (pin "13") (pinfunction "D13_13") (pintype "passive"))
    )
    (net (code "102") (name "Net-(U9-D14)") (class "Default")
      (node (ref "R45") (pin "2") (pinfunction "2_2") (pintype "passive"))
      (node (ref "U9") (pin "14") (pinfunction "D14_14") (pintype "passive"))
    )
    (net (code "103") (name "Net-(U9-D17)") (class "Default")
      (node (ref "R51") (pin "2") (pinfunction "2_2") (pintype "passive"))
      (node (ref "U9") (pin "17") (pinfunction "D17_17") (pintype "passive"))
    )
    (net (code "104") (name "Net-(U9-D18)") (class "Default")
      (node (ref "R53") (pin "2") (pinfunction "2_2") (pintype "passive"))
      (node (ref "U9") (pin "18") (pinfunction "D18_18") (pintype "passive"))
    )
    (net (code "105") (name "Net-(U9-D19)") (class "Default")
      (node (ref "R54") (pin "2") (pinfunction "2_2") (pintype "passive"))
      (node (ref "U9") (pin "19") (pinfunction "D19_19") (pintype "passive"))
    )
    (net (code "106") (name "Net-(U9-D20)") (class "Default")
      (node (ref "R55") (pin "2") (pinfunction "2_2") (pintype "passive"))
      (node (ref "U9") (pin "20") (pinfunction "D20_20") (pintype "passive"))
    )
    (net (code "107") (name "Net-(U9-D21)") (class "Default")
      (node (ref "R56") (pin "2") (pinfunction "2_2") (pintype "passive"))
      (node (ref "U9") (pin "21") (pinfunction "D21_21") (pintype "passive"))
    )
    (net (code "108") (name "Net-(U9-D22)") (class "Default")
      (node (ref "R57") (pin "2") (pinfunction "2_2") (pintype "passive"))
      (node (ref "U9") (pin "22") (pinfunction "D22_22") (pintype "passive"))
    )
    (net (code "109") (name "Net-(U9-D23)") (class "Default")
      (node (ref "R59") (pin "2") (pinfunction "2_2") (pintype "passive"))
      (node (ref "U9") (pin "23") (pinfunction "D23_23") (pintype "passive"))
    )
    (net (code "110") (name "Net-(U9-D32)") (class "Default")
      (node (ref "R60") (pin "1") (pinfunction "1_1") (pintype "passive"))
      (node (ref "U9") (pin "32") (pinfunction "D32_32") (pintype "passive"))
    )
    (net (code "111") (name "Net-(U10-+IN)") (class "Default")
      (node (ref "R44") (pin "2") (pinfunction "2_2") (pintype "passive"))
      (node (ref "U10") (pin "8") (pinfunction "+IN_8") (pintype "tri_state"))
    )
    (net (code "112") (name "Net-(U10-+OUT)") (class "Default")
      (node (ref "C53") (pin "2") (pinfunction "2_2") (pintype "passive"))
      (node (ref "R46") (pin "2") (pinfunction "2_2") (pintype "passive"))
      (node (ref "U10") (pin "4") (pinfunction "+OUT_4") (pintype "passive"))
    )
    (net (code "113") (name "Net-(U10--OUT)") (class "Default")
      (node (ref "C61") (pin "1") (pinfunction "1_1") (pintype "passive"))
      (node (ref "R52") (pin "2") (pinfunction "2_2") (pintype "passive"))
      (node (ref "U10") (pin "5") (pinfunction "-OUT_5") (pintype "passive"))
    )
    (net (code "114") (name "Net-(U10-VOCM)") (class "Default")
      (node (ref "R40") (pin "2") (pinfunction "2_2") (pintype "passive"))
      (node (ref "U10") (pin "2") (pinfunction "VOCM_2") (pintype "passive"))
    )
    (net (code "115") (name "Net-(U11-VOUT)") (class "Default")
      (node (ref "C58") (pin "2") (pinfunction "2_2") (pintype "passive"))
      (node (ref "U11") (pin "5") (pinfunction "VOUT_5") (pintype "power_in"))
      (node (ref "W5") (pin "1") (pinfunction "C1_1") (pintype "passive"))
    )
    (net (code "116") (name "Net-(U12C-A_0)") (class "Default")
      (node (ref "R59") (pin "1") (pinfunction "1_1") (pintype "passive"))
      (node (ref "U12") (pin "2") (pinfunction "A_0_2") (pintype "passive"))
    )
    (net (code "117") (name "Net-(U12C-A_1)") (class "Default")
      (node (ref "R57") (pin "1") (pinfunction "1_1") (pintype "passive"))
      (node (ref "U12") (pin "3") (pinfunction "A_1_3") (pintype "passive"))
    )
    (net (code "118") (name "Net-(U12C-A_2)") (class "Default")
      (node (ref "R56") (pin "1") (pinfunction "1_1") (pintype "passive"))
      (node (ref "U12") (pin "4") (pinfunction "A_2_4") (pintype "passive"))
    )
    (net (code "119") (name "Net-(U12C-A_3)") (class "Default")
      (node (ref "R55") (pin "1") (pinfunction "1_1") (pintype "passive"))
      (node (ref "U12") (pin "5") (pinfunction "A_3_5") (pintype "passive"))
    )
    (net (code "120") (name "Net-(U12C-A_4)") (class "Default")
      (node (ref "R54") (pin "1") (pinfunction "1_1") (pintype "passive"))
      (node (ref "U12") (pin "6") (pinfunction "A_4_6") (pintype "passive"))
    )
    (net (code "121") (name "Net-(U12C-A_5)") (class "Default")
      (node (ref "R53") (pin "1") (pinfunction "1_1") (pintype "passive"))
      (node (ref "U12") (pin "7") (pinfunction "A_5_7") (pintype "passive"))
    )
    (net (code "122") (name "Net-(U12C-A_6)") (class "Default")
      (node (ref "R51") (pin "1") (pinfunction "1_1") (pintype "passive"))
      (node (ref "U12") (pin "8") (pinfunction "A_6_8") (pintype "passive"))
    )
    (net (code "123") (name "Net-(U12C-A_7)") (class "Default")
      (node (ref "R50") (pin "1") (pinfunction "1_1") (pintype "passive"))
      (node (ref "U12") (pin "9") (pinfunction "A_7_9") (pintype "passive"))
    )
    (net (code "124") (name "Net-(U12C-B_0)") (class "Default")
      (node (ref "U12") (pin "18") (pinfunction "B_0_18") (pintype "passive"))
      (node (ref "U6") (pin "18") (pinfunction "D0_18") (pintype "output"))
    )
    (net (code "125") (name "Net-(U12C-B_1)") (class "Default")
      (node (ref "U12") (pin "17") (pinfunction "B_1_17") (pintype "passive"))
      (node (ref "U6") (pin "19") (pinfunction "D1_19") (pintype "output"))
    )
    (net (code "126") (name "Net-(U12C-B_2)") (class "Default")
      (node (ref "U12") (pin "16") (pinfunction "B_2_16") (pintype "passive"))
      (node (ref "U6") (pin "20") (pinfunction "D2_20") (pintype "output"))
    )
    (net (code "127") (name "Net-(U12C-B_3)") (class "Default")
      (node (ref "U12") (pin "15") (pinfunction "B_3_15") (pintype "passive"))
      (node (ref "U6") (pin "21") (pinfunction "D3_21") (pintype "output"))
    )
    (net (code "128") (name "Net-(U12C-B_4)") (class "Default")
      (node (ref "U12") (pin "14") (pinfunction "B_4_14") (pintype "passive"))
      (node (ref "U6") (pin "22") (pinfunction "D4_22") (pintype "output"))
    )
    (net (code "129") (name "Net-(U12C-B_5)") (class "Default")
      (node (ref "U12") (pin "13") (pinfunction "B_5_13") (pintype "passive"))
      (node (ref "U6") (pin "26") (pinfunction "D5_26") (pintype "output"))
    )
    (net (code "130") (name "Net-(U12C-B_6)") (class "Default")
      (node (ref "U12") (pin "12") (pinfunction "B_6_12") (pintype "passive"))
      (node (ref "U6") (pin "27") (pinfunction "D6_27") (pintype "output"))
    )
    (net (code "131") (name "Net-(U12C-B_7)") (class "Default")
      (node (ref "U12") (pin "11") (pinfunction "B_7_11") (pintype "passive"))
      (node (ref "U6") (pin "28") (pinfunction "D7_28") (pintype "output"))
    )
    (net (code "132") (name "Net-(W3-C1)") (class "Default")
      (node (ref "C32") (pin "1") (pinfunction "1_1") (pintype "passive"))
      (node (ref "U4") (pin "2") (pinfunction "VOUT_2") (pintype "power_in"))
      (node (ref "U4") (pin "4") (pinfunction "VOUT_4") (pintype "power_in"))
      (node (ref "W3") (pin "1") (pinfunction "C1_1") (pintype "passive"))
    )
    (net (code "133") (name "VIN") (class "Default")
      (node (ref "C2") (pin "1") (pinfunction "1_1") (pintype "passive"))
      (node (ref "C31") (pin "1") (pinfunction "1_1") (pintype "passive"))
      (node (ref "C36") (pin "2") (pinfunction "2_2") (pintype "passive"))
      (node (ref "C37") (pin "1") (pinfunction "1_1") (pintype "passive"))
      (node (ref "C38") (pin "1") (pinfunction "1_1") (pintype "passive"))
      (node (ref "C39") (pin "1") (pinfunction "1_1") (pintype "passive"))
      (node (ref "C51") (pin "2") (pinfunction "2_2") (pintype "passive"))
      (node (ref "C57") (pin "2") (pinfunction "2_2") (pintype "passive"))
      (node (ref "L2") (pin "2") (pinfunction "2_2") (pintype "passive"))
      (node (ref "P5") (pin "1") (pinfunction "1_1") (pintype "passive"))
      (node (ref "P5") (pin "2") (pinfunction "2_2") (pintype "passive"))
      (node (ref "P6") (pin "6") (pinfunction "6_6") (pintype "passive"))
      (node (ref "TP1") (pin "1") (pinfunction "1_1") (pintype "passive"))
      (node (ref "U11") (pin "1") (pinfunction "VIN_1") (pintype "power_in"))
      (node (ref "U11") (pin "3") (pinfunction "EN_3") (pintype "input"))
      (node (ref "U2") (pin "1") (pinfunction "EN+_1") (pintype "input"))
      (node (ref "U2") (pin "11") (pinfunction "VIN_11") (pintype "power_in"))
      (node (ref "U2") (pin "13") (pinfunction "EN-_13") (pintype "input"))
      (node (ref "U4") (pin "3") (pinfunction "VIN_3") (pintype "power_in"))
      (node (ref "U7") (pin "1") (pinfunction "VIN_1") (pintype "power_in"))
      (node (ref "U7") (pin "3") (pinfunction "EN_3") (pintype "input"))
    )
    (net (code "134") (name "VLASER") (class "Default")
      (node (ref "C29") (pin "2") (pinfunction "2_2") (pintype "passive"))
      (node (ref "D3") (pin "2") (pinfunction "K_2") (pintype "passive"))
      (node (ref "L1") (pin "1") (pinfunction "1_1") (pintype "passive"))
      (node (ref "R18") (pin "2") (pinfunction "2_2") (pintype "passive"))
      (node (ref "R22") (pin "2") (pinfunction "2_2") (pintype "passive"))
      (node (ref "TP6") (pin "1") (pinfunction "1_1") (pintype "passive"))
    )
    (net (code "135") (name "unconnected-(DD1-PA1-Pad11)") (class "Default")
      (node (ref "DD1") (pin "11") (pinfunction "PA1_11") (pintype "passive"))
    )
    (net (code "136") (name "unconnected-(DD1-PA2-Pad12)") (class "Default")
      (node (ref "DD1") (pin "12") (pinfunction "PA2_12") (pintype "passive"))
    )
    (net (code "137") (name "unconnected-(DD1-PA3-Pad13)") (class "Default")
      (node (ref "DD1") (pin "13") (pinfunction "PA3_13") (pintype "passive"))
    )
    (net (code "138") (name "unconnected-(DD1-PA4-Pad14)") (class "Default")
      (node (ref "DD1") (pin "14") (pinfunction "PA4_14") (pintype "passive"))
    )
    (net (code "139") (name "unconnected-(DD1-PA6-Pad16)") (class "Default")
      (node (ref "DD1") (pin "16") (pinfunction "PA6_16") (pintype "passive"))
    )
    (net (code "140") (name "unconnected-(DD1-PA8-Pad29)") (class "Default")
      (node (ref "DD1") (pin "29") (pinfunction "PA8_29") (pintype "passive"))
    )
    (net (code "141") (name "unconnected-(DD1-PA9-Pad30)") (class "Default")
      (node (ref "DD1") (pin "30") (pinfunction "PA9_30") (pintype "passive"))
    )
    (net (code "142") (name "unconnected-(DD1-PA11-Pad32)") (class "Default")
      (node (ref "DD1") (pin "32") (pinfunction "PA11_32") (pintype "passive"))
    )
    (net (code "143") (name "unconnected-(DD1-PA12-Pad33)") (class "Default")
      (node (ref "DD1") (pin "33") (pinfunction "PA12_33") (pintype "passive"))
    )
    (net (code "144") (name "unconnected-(DD1-PA15-Pad38)") (class "Default")
      (node (ref "DD1") (pin "38") (pinfunction "PA15_38") (pintype "passive"))
    )
    (net (code "145") (name "unconnected-(DD1-PB0-Pad18)") (class "Default")
      (node (ref "DD1") (pin "18") (pinfunction "PB0_18") (pintype "passive"))
    )
    (net (code "146") (name "unconnected-(DD1-PB1-Pad19)") (class "Default")
      (node (ref "DD1") (pin "19") (pinfunction "PB1_19") (pintype "passive"))
    )
    (net (code "147") (name "unconnected-(DD1-PB2-Pad20)") (class "Default")
      (node (ref "DD1") (pin "20") (pinfunction "PB2_20") (pintype "passive"))
    )
    (net (code "148") (name "unconnected-(DD1-PB5-Pad41)") (class "Default")
      (node (ref "DD1") (pin "41") (pinfunction "PB5_41") (pintype "passive"))
    )
    (net (code "149") (name "unconnected-(DD1-PB6-Pad42)") (class "Default")
      (node (ref "DD1") (pin "42") (pinfunction "PB6_42") (pintype "passive"))
    )
    (net (code "150") (name "unconnected-(DD1-PB7-Pad43)") (class "Default")
      (node (ref "DD1") (pin "43") (pinfunction "PB7_43") (pintype "passive"))
    )
    (net (code "151") (name "unconnected-(DD1-PB8-Pad45)") (class "Default")
      (node (ref "DD1") (pin "45") (pinfunction "PB8_45") (pintype "passive"))
    )
    (net (code "152") (name "unconnected-(DD1-PB9-Pad46)") (class "Default")
      (node (ref "DD1") (pin "46") (pinfunction "PB9_46") (pintype "passive"))
    )
    (net (code "153") (name "unconnected-(DD1-PB10-Pad21)") (class "Default")
      (node (ref "DD1") (pin "21") (pinfunction "PB10_21") (pintype "passive"))
    )
    (net (code "154") (name "unconnected-(DD1-PB11-Pad22)") (class "Default")
      (node (ref "DD1") (pin "22") (pinfunction "PB11_22") (pintype "passive"))
    )
    (net (code "155") (name "unconnected-(DD1-PB12-Pad25)") (class "Default")
      (node (ref "DD1") (pin "25") (pinfunction "PB12_25") (pintype "passive"))
    )
    (net (code "156") (name "unconnected-(DD1-PB13-Pad26)") (class "Default")
      (node (ref "DD1") (pin "26") (pinfunction "PB13_26") (pintype "passive"))
    )
    (net (code "157") (name "unconnected-(DD1-PB14-Pad27)") (class "Default")
      (node (ref "DD1") (pin "27") (pinfunction "PB14_27") (pintype "passive"))
    )
    (net (code "158") (name "unconnected-(DD1-PB15-Pad28)") (class "Default")
      (node (ref "DD1") (pin "28") (pinfunction "PB15_28") (pintype "passive"))
    )
    (net (code "159") (name "unconnected-(DD1-PC13-Pad2)") (class "Default")
      (node (ref "DD1") (pin "2") (pinfunction "PC13_2") (pintype "passive"))
    )
    (net (code "160") (name "unconnected-(DD1-PC14-Pad3)") (class "Default")
      (node (ref "DD1") (pin "3") (pinfunction "PC14_3") (pintype "passive"))
    )
    (net (code "161") (name "unconnected-(DD1-PC15-Pad4)") (class "Default")
      (node (ref "DD1") (pin "4") (pinfunction "PC15_4") (pintype "passive"))
    )
    (net (code "162") (name "unconnected-(U1A-+IN1-Pad3)") (class "Default")
      (node (ref "U1") (pin "3") (pinfunction "+IN1_3") (pintype "tri_state+no_connect"))
    )
    (net (code "163") (name "unconnected-(U1A--IN1-Pad2)") (class "Default")
      (node (ref "U1") (pin "2") (pinfunction "-IN1_2") (pintype "tri_state+no_connect"))
    )
    (net (code "164") (name "unconnected-(U1A-VOUT1-Pad1)") (class "Default")
      (node (ref "U1") (pin "1") (pinfunction "VOUT1_1") (pintype "passive+no_connect"))
    )
    (net (code "165") (name "unconnected-(U2-NC-Pad8)") (class "Default")
      (node (ref "U2") (pin "8") (pinfunction "NC_8") (pintype "passive+no_connect"))
    )
    (net (code "166") (name "unconnected-(U2-NC-Pad9)") (class "Default")
      (node (ref "U2") (pin "9") (pinfunction "NC_9") (pintype "passive+no_connect"))
    )
    (net (code "167") (name "unconnected-(U6-CLKOUT--Pad29)") (class "Default")
      (node (ref "U6") (pin "29") (pinfunction "CLKOUT-_29") (pintype "passive+no_connect"))
    )
    (net (code "168") (name "unconnected-(U6-OF-Pad43)") (class "Default")
      (node (ref "U6") (pin "43") (pinfunction "OF_43") (pintype "output+no_connect"))
    )
    (net (code "169") (name "unconnected-(U7-NC-Pad4)") (class "Default")
      (node (ref "U7") (pin "4") (pinfunction "NC_4") (pintype "passive"))
    )
    (net (code "170") (name "unconnected-(U9-D1-Pad1)") (class "Default")
      (node (ref "U9") (pin "1") (pinfunction "D1_1") (pintype "passive"))
    )
    (net (code "171") (name "unconnected-(U9-D2-Pad2)") (class "Default")
      (node (ref "U9") (pin "2") (pinfunction "D2_2") (pintype "passive"))
    )
    (net (code "172") (name "unconnected-(U9-D3-Pad3)") (class "Default")
      (node (ref "U9") (pin "3") (pinfunction "D3_3") (pintype "passive"))
    )
    (net (code "173") (name "unconnected-(U9-D4-Pad4)") (class "Default")
      (node (ref "U9") (pin "4") (pinfunction "D4_4") (pintype "passive"))
    )
    (net (code "174") (name "unconnected-(U9-D5-Pad5)") (class "Default")
      (node (ref "U9") (pin "5") (pinfunction "D5_5") (pintype "passive"))
    )
    (net (code "175") (name "unconnected-(U9-D6-Pad6)") (class "Default")
      (node (ref "U9") (pin "6") (pinfunction "D6_6") (pintype "passive"))
    )
    (net (code "176") (name "unconnected-(U9-D26-Pad26)") (class "Default")
      (node (ref "U9") (pin "26") (pinfunction "D26_26") (pintype "passive"))
    )
    (net (code "177") (name "unconnected-(U9-D27-Pad27)") (class "Default")
      (node (ref "U9") (pin "27") (pinfunction "D27_27") (pintype "passive"))
    )
    (net (code "178") (name "unconnected-(U9-D28-Pad28)") (class "Default")
      (node (ref "U9") (pin "28") (pinfunction "D28_28") (pintype "passive"))
    )
    (net (code "179") (name "unconnected-(U9-D30-Pad30)") (class "Default")
      (node (ref "U9") (pin "30") (pinfunction "D30_30") (pintype "passive"))
    )
    (net (code "180") (name "unconnected-(U9-D31-Pad31)") (class "Default")
      (node (ref "U9") (pin "31") (pinfunction "D31_31") (pintype "passive"))
    )
    (net (code "181") (name "unconnected-(U9-D33-Pad33)") (class "Default")
      (node (ref "U9") (pin "33") (pinfunction "D33_33") (pintype "passive"))
    )
    (net (code "182") (name "unconnected-(U9-D34-Pad34)") (class "Default")
      (node (ref "U9") (pin "34") (pinfunction "D34_34") (pintype "passive"))
    )
    (net (code "183") (name "unconnected-(U9-D35-Pad35)") (class "Default")
      (node (ref "U9") (pin "35") (pinfunction "D35_35") (pintype "passive"))
    )
    (net (code "184") (name "unconnected-(U9-D36-Pad36)") (class "Default")
      (node (ref "U9") (pin "36") (pinfunction "D36_36") (pintype "passive"))
    )
    (net (code "185") (name "unconnected-(U9-D37-Pad37)") (class "Default")
      (node (ref "U9") (pin "37") (pinfunction "D37_37") (pintype "passive"))
    )
    (net (code "186") (name "unconnected-(U9-D38-Pad38)") (class "Default")
      (node (ref "U9") (pin "38") (pinfunction "D38_38") (pintype "passive"))
    )
    (net (code "187") (name "unconnected-(U9-D39-Pad39)") (class "Default")
      (node (ref "U9") (pin "39") (pinfunction "D39_39") (pintype "passive"))
    )
    (net (code "188") (name "unconnected-(U9-D40-Pad40)") (class "Default")
      (node (ref "U9") (pin "40") (pinfunction "D40_40") (pintype "passive"))
    )
    (net (code "189") (name "unconnected-(U9-D41-Pad41)") (class "Default")
      (node (ref "U9") (pin "41") (pinfunction "D41_41") (pintype "passive"))
    )
    (net (code "190") (name "unconnected-(U9-D42-Pad42)") (class "Default")
      (node (ref "U9") (pin "42") (pinfunction "D42_42") (pintype "passive"))
    )
    (net (code "191") (name "unconnected-(U9-D43-Pad43)") (class "Default")
      (node (ref "U9") (pin "43") (pinfunction "D43_43") (pintype "passive"))
    )
    (net (code "192") (name "unconnected-(U9-D44-Pad44)") (class "Default")
      (node (ref "U9") (pin "44") (pinfunction "D44_44") (pintype "passive"))
    )
    (net (code "193") (name "unconnected-(U9-D45-Pad45)") (class "Default")
      (node (ref "U9") (pin "45") (pinfunction "D45_45") (pintype "passive"))
    )
    (net (code "194") (name "unconnected-(U9-D46-Pad46)") (class "Default")
      (node (ref "U9") (pin "46") (pinfunction "D46_46") (pintype "passive"))
    )
    (net (code "195") (name "unconnected-(U9-D47-Pad47)") (class "Default")
      (node (ref "U9") (pin "47") (pinfunction "D47_47") (pintype "passive"))
    )
    (net (code "196") (name "unconnected-(U9-D48-Pad48)") (class "Default")
      (node (ref "U9") (pin "48") (pinfunction "D48_48") (pintype "passive"))
    )
    (net (code "197") (name "unconnected-(U9-VU-Pad24)") (class "Default")
      (node (ref "U9") (pin "24") (pinfunction "VU_24") (pintype "passive"))
    )
    (net (code "198") (name "unconnected-(U10-~{SHDN}-Pad7)") (class "Default")
      (node (ref "U10") (pin "7") (pinfunction "~{SHDN}_7") (pintype "input+no_connect"))
    )
    (net (code "199") (name "unconnected-(U11-NC-Pad4)") (class "Default")
      (node (ref "U11") (pin "4") (pinfunction "NC_4") (pintype "passive+no_connect"))
    )
  )
)
